# GaN_Fet_ESC_V0_2.net
KiCad netlist of a schematic drawn in EAGLE
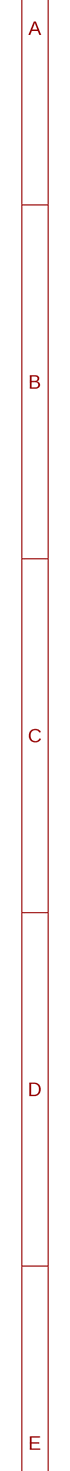
[diagram p0: schematic, sheet 1, part 1 of 2]
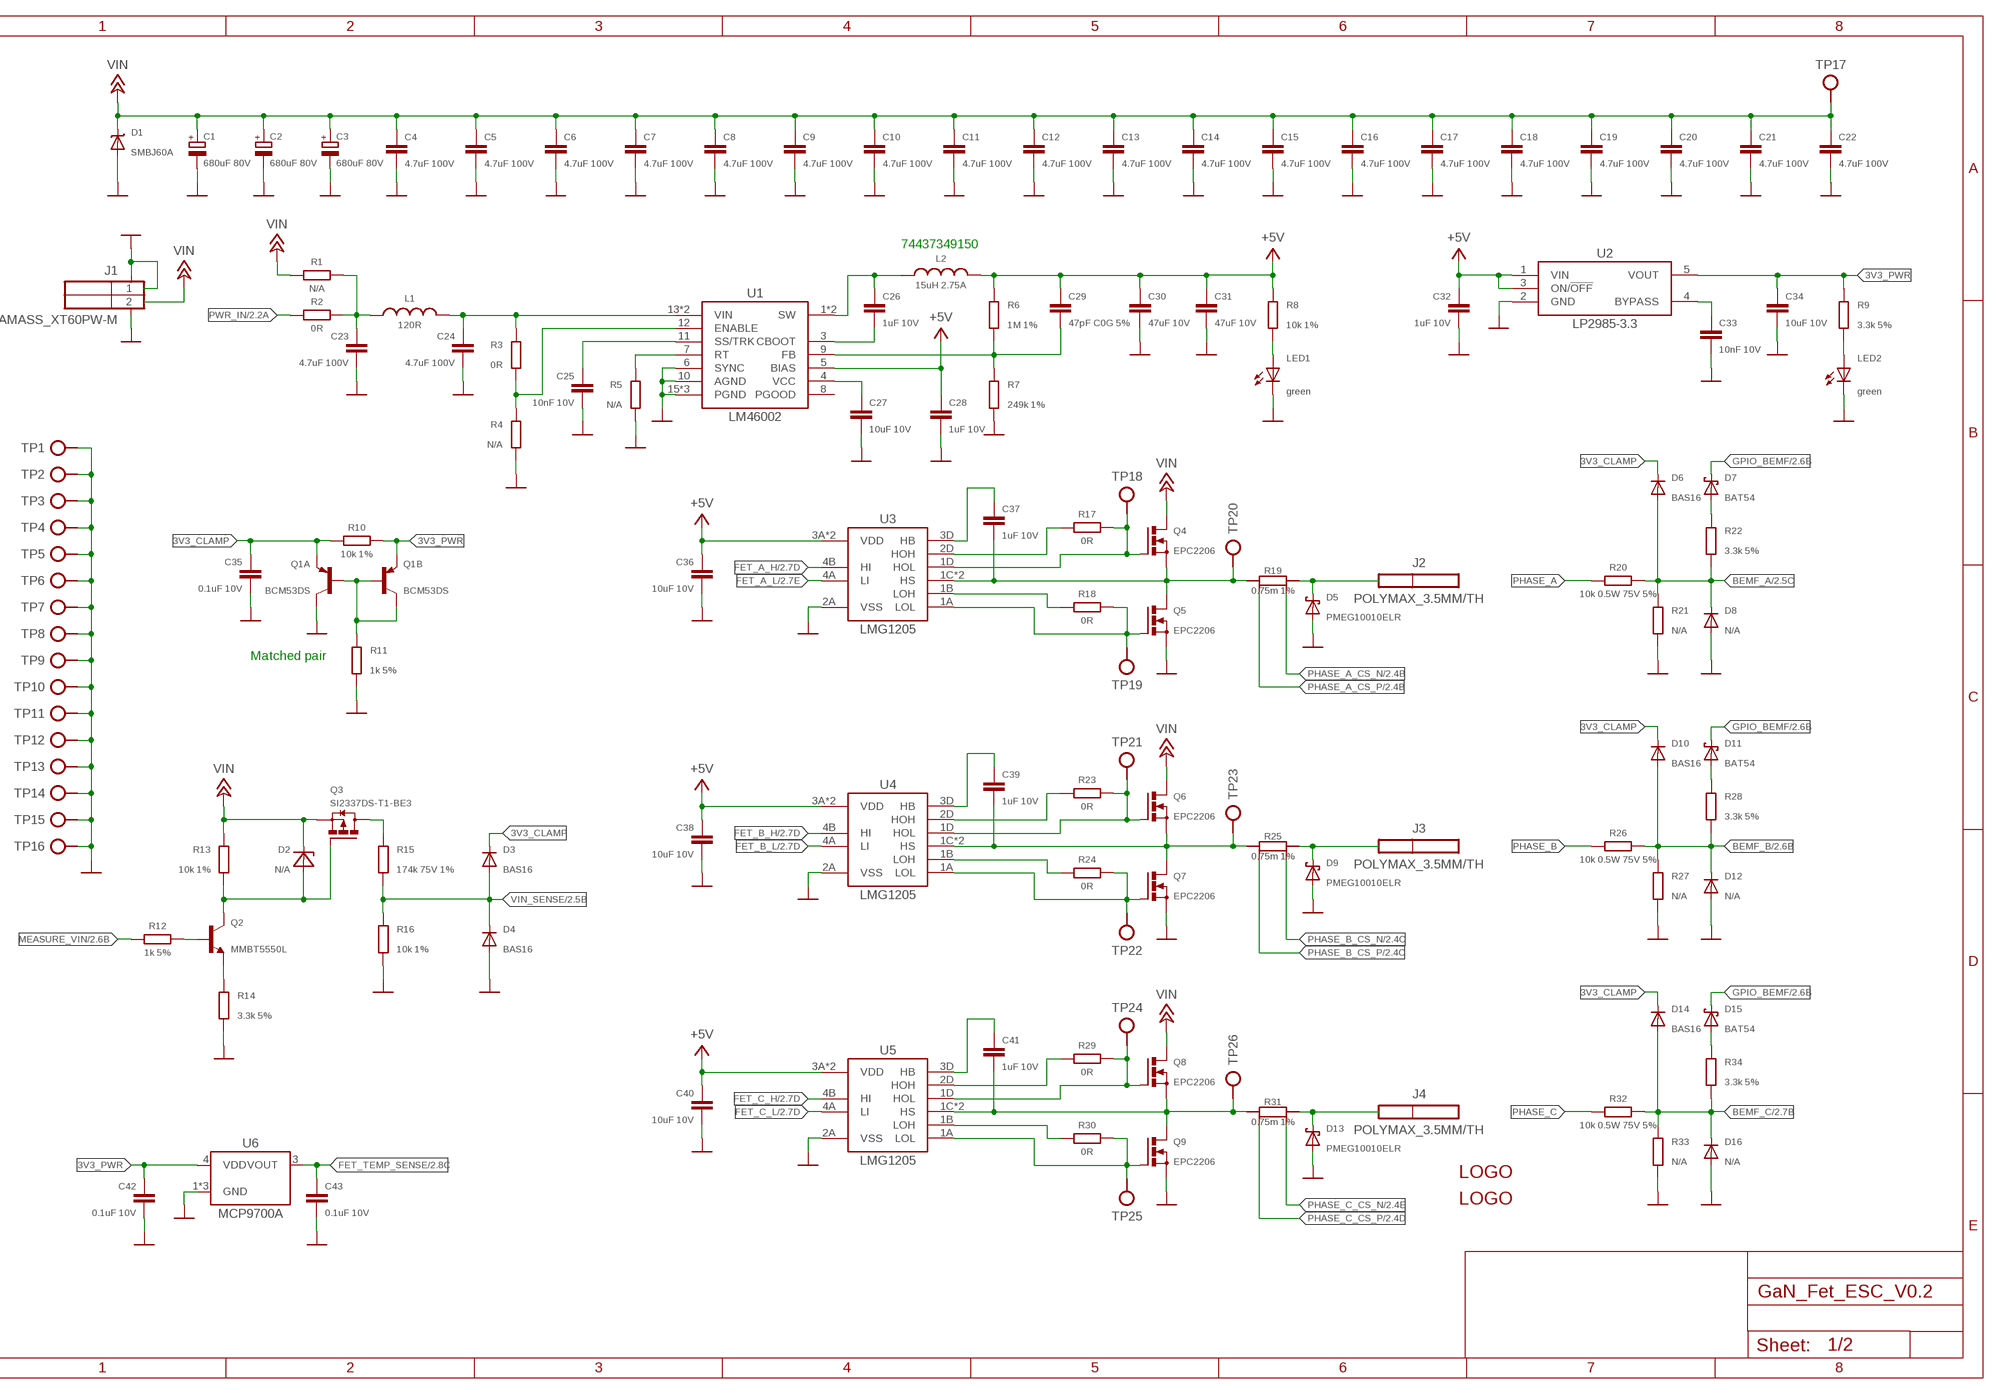
[diagram p1: schematic, sheet 1, part 2 of 2]
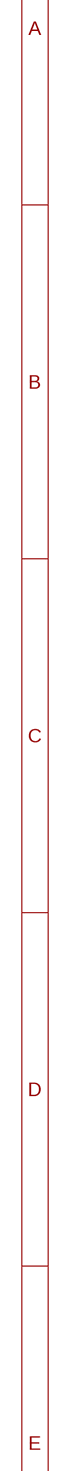
[diagram p2: schematic, sheet 2, part 1 of 2]
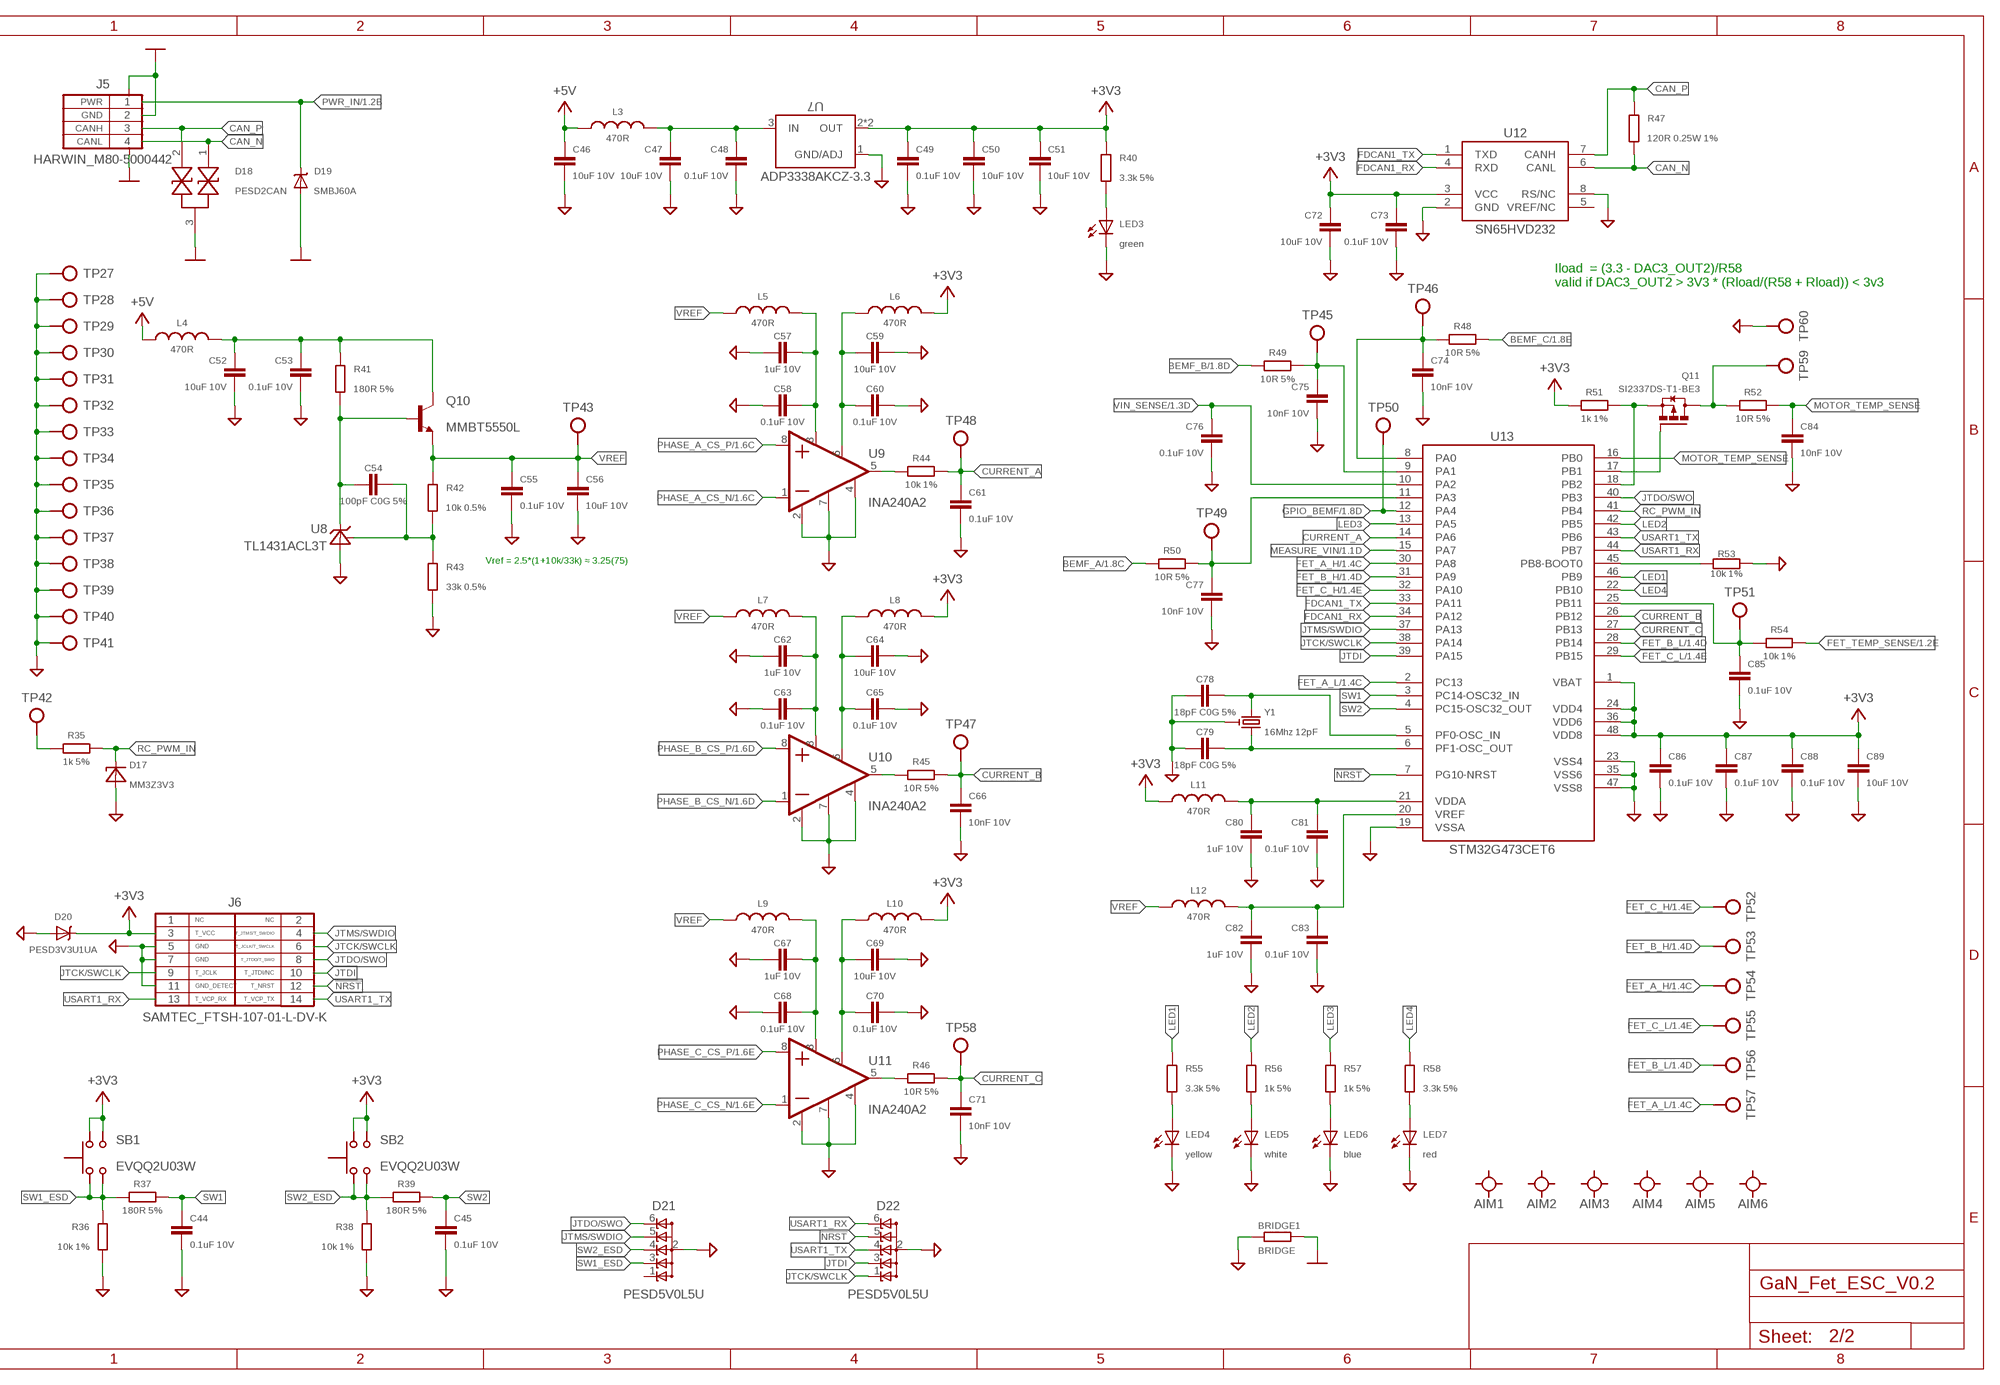
[diagram p3: schematic, sheet 2, part 2 of 2]

(export (version "E")
  (design (tool "Eeschema 10.0.6"))
  (components
    (comp (ref "C1")
      (value "680uF 80V")
      (footprint "eagle-import:C_7.50_16_26.5_4")
      (libsource (lib "eagle-import") (part "CAPACITOR_ELECTROLYTIC4"))
    )
    (comp (ref "C2")
      (value "680uF 80V")
      (footprint "eagle-import:C_7.50_16_26.5_6")
      (libsource (lib "eagle-import") (part "CAPACITOR_ELECTROLYTIC6"))
    )
    (comp (ref "C3")
      (value "680uF 80V")
      (footprint "eagle-import:C_7.50_16_26.5_5")
      (libsource (lib "eagle-import") (part "CAPACITOR_ELECTROLYTIC5"))
    )
    (comp (ref "C4")
      (value "4.7uF 100V")
      (footprint "eagle-import:C1210")
      (libsource (lib "eagle-import") (part "CAPACITOR_CERAMIC/1210"))
    )
    (comp (ref "C5")
      (value "4.7uF 100V")
      (footprint "eagle-import:C1210")
      (libsource (lib "eagle-import") (part "CAPACITOR_CERAMIC/1210"))
    )
    (comp (ref "C6")
      (value "4.7uF 100V")
      (footprint "eagle-import:C1210")
      (libsource (lib "eagle-import") (part "CAPACITOR_CERAMIC/1210"))
    )
    (comp (ref "C7")
      (value "4.7uF 100V")
      (footprint "eagle-import:C1210")
      (libsource (lib "eagle-import") (part "CAPACITOR_CERAMIC/1210"))
    )
    (comp (ref "C8")
      (value "4.7uF 100V")
      (footprint "eagle-import:C1210")
      (libsource (lib "eagle-import") (part "CAPACITOR_CERAMIC/1210"))
    )
    (comp (ref "C9")
      (value "4.7uF 100V")
      (footprint "eagle-import:C1210")
      (libsource (lib "eagle-import") (part "CAPACITOR_CERAMIC/1210"))
    )
    (comp (ref "C10")
      (value "4.7uF 100V")
      (footprint "eagle-import:C1210")
      (libsource (lib "eagle-import") (part "CAPACITOR_CERAMIC/1210"))
    )
    (comp (ref "C11")
      (value "4.7uF 100V")
      (footprint "eagle-import:C1210")
      (libsource (lib "eagle-import") (part "CAPACITOR_CERAMIC/1210"))
    )
    (comp (ref "C12")
      (value "4.7uF 100V")
      (footprint "eagle-import:C1210")
      (libsource (lib "eagle-import") (part "CAPACITOR_CERAMIC/1210"))
    )
    (comp (ref "C13")
      (value "4.7uF 100V")
      (footprint "eagle-import:C1210")
      (libsource (lib "eagle-import") (part "CAPACITOR_CERAMIC/1210"))
    )
    (comp (ref "C14")
      (value "4.7uF 100V")
      (footprint "eagle-import:C1210")
      (libsource (lib "eagle-import") (part "CAPACITOR_CERAMIC/1210"))
    )
    (comp (ref "C15")
      (value "4.7uF 100V")
      (footprint "eagle-import:C1210")
      (libsource (lib "eagle-import") (part "CAPACITOR_CERAMIC/1210"))
    )
    (comp (ref "C16")
      (value "4.7uF 100V")
      (footprint "eagle-import:C1210")
      (libsource (lib "eagle-import") (part "CAPACITOR_CERAMIC/1210"))
    )
    (comp (ref "C17")
      (value "4.7uF 100V")
      (footprint "eagle-import:C1210")
      (libsource (lib "eagle-import") (part "CAPACITOR_CERAMIC/1210"))
    )
    (comp (ref "C18")
      (value "4.7uF 100V")
      (footprint "eagle-import:C1210")
      (libsource (lib "eagle-import") (part "CAPACITOR_CERAMIC/1210"))
    )
    (comp (ref "C19")
      (value "4.7uF 100V")
      (footprint "eagle-import:C1210")
      (libsource (lib "eagle-import") (part "CAPACITOR_CERAMIC/1210"))
    )
    (comp (ref "C20")
      (value "4.7uF 100V")
      (footprint "eagle-import:C1210")
      (libsource (lib "eagle-import") (part "CAPACITOR_CERAMIC/1210"))
    )
    (comp (ref "C21")
      (value "4.7uF 100V")
      (footprint "eagle-import:C1210")
      (libsource (lib "eagle-import") (part "CAPACITOR_CERAMIC/1210"))
    )
    (comp (ref "C22")
      (value "4.7uF 100V")
      (footprint "eagle-import:C1210")
      (libsource (lib "eagle-import") (part "CAPACITOR_CERAMIC/1210"))
    )
    (comp (ref "C23")
      (value "4.7uF 100V")
      (footprint "eagle-import:C1210")
      (libsource (lib "eagle-import") (part "CAPACITOR_CERAMIC/1210"))
    )
    (comp (ref "C24")
      (value "4.7uF 100V")
      (footprint "eagle-import:C1210")
      (libsource (lib "eagle-import") (part "CAPACITOR_CERAMIC/1210"))
    )
    (comp (ref "C25")
      (value "10nF 10V")
      (footprint "eagle-import:C0402")
      (libsource (lib "eagle-import") (part "CAPACITOR_CERAMIC/0402"))
    )
    (comp (ref "C26")
      (value "1uF 10V")
      (footprint "eagle-import:C0402")
      (libsource (lib "eagle-import") (part "CAPACITOR_CERAMIC/0402"))
    )
    (comp (ref "C27")
      (value "10uF 10V")
      (footprint "eagle-import:C0603")
      (libsource (lib "eagle-import") (part "CAPACITOR_CERAMIC/0603"))
    )
    (comp (ref "C28")
      (value "1uF 10V")
      (footprint "eagle-import:C0402")
      (libsource (lib "eagle-import") (part "CAPACITOR_CERAMIC/0402"))
    )
    (comp (ref "C29")
      (value "47pF C0G 5%")
      (footprint "eagle-import:C0402")
      (libsource (lib "eagle-import") (part "CAPACITOR_CERAMIC/0402"))
    )
    (comp (ref "C30")
      (value "47uF 10V")
      (footprint "eagle-import:C1206")
      (libsource (lib "eagle-import") (part "CAPACITOR_CERAMIC/1206"))
    )
    (comp (ref "C31")
      (value "47uF 10V")
      (footprint "eagle-import:C1206")
      (libsource (lib "eagle-import") (part "CAPACITOR_CERAMIC/1206"))
    )
    (comp (ref "C32")
      (value "1uF 10V")
      (footprint "eagle-import:C0402")
      (libsource (lib "eagle-import") (part "CAPACITOR_CERAMIC/0402"))
    )
    (comp (ref "C33")
      (value "10nF 10V")
      (footprint "eagle-import:C0402")
      (libsource (lib "eagle-import") (part "CAPACITOR_CERAMIC/0402"))
    )
    (comp (ref "C34")
      (value "10uF 10V")
      (footprint "eagle-import:C0603")
      (libsource (lib "eagle-import") (part "CAPACITOR_CERAMIC/0603"))
    )
    (comp (ref "C35")
      (value "0.1uF 10V")
      (footprint "eagle-import:C0402")
      (libsource (lib "eagle-import") (part "CAPACITOR_CERAMIC/0402"))
    )
    (comp (ref "C36")
      (value "10uF 10V")
      (footprint "eagle-import:C0603")
      (libsource (lib "eagle-import") (part "CAPACITOR_CERAMIC/0603"))
    )
    (comp (ref "C37")
      (value "1uF 10V")
      (footprint "eagle-import:C0402")
      (libsource (lib "eagle-import") (part "CAPACITOR_CERAMIC/0402"))
    )
    (comp (ref "C38")
      (value "10uF 10V")
      (footprint "eagle-import:C0603")
      (libsource (lib "eagle-import") (part "CAPACITOR_CERAMIC/0603"))
    )
    (comp (ref "C39")
      (value "1uF 10V")
      (footprint "eagle-import:C0402")
      (libsource (lib "eagle-import") (part "CAPACITOR_CERAMIC/0402"))
    )
    (comp (ref "C40")
      (value "10uF 10V")
      (footprint "eagle-import:C0603")
      (libsource (lib "eagle-import") (part "CAPACITOR_CERAMIC/0603"))
    )
    (comp (ref "C41")
      (value "1uF 10V")
      (footprint "eagle-import:C0402")
      (libsource (lib "eagle-import") (part "CAPACITOR_CERAMIC/0402"))
    )
    (comp (ref "C42")
      (value "0.1uF 10V")
      (footprint "eagle-import:C0402")
      (libsource (lib "eagle-import") (part "CAPACITOR_CERAMIC/0402"))
    )
    (comp (ref "C43")
      (value "0.1uF 10V")
      (footprint "eagle-import:C0402")
      (libsource (lib "eagle-import") (part "CAPACITOR_CERAMIC/0402"))
    )
    (comp (ref "D1")
      (value "SMBJ60A")
      (footprint "eagle-import:DO214AA(SMB)")
      (libsource (lib "eagle-import") (part "DIODE_TVS_UNIDIR/SMB"))
    )
    (comp (ref "D2")
      (value "N/A")
      (footprint "eagle-import:SOD323F")
      (libsource (lib "eagle-import") (part "DIODE_ZENER"))
    )
    (comp (ref "D3")
      (value "BAS16")
      (footprint "eagle-import:SOD523")
      (libsource (lib "eagle-import") (part "DIODE/SOD523"))
    )
    (comp (ref "D4")
      (value "BAS16")
      (footprint "eagle-import:SOD523")
      (libsource (lib "eagle-import") (part "DIODE/SOD523"))
    )
    (comp (ref "D5")
      (value "PMEG10010ELR")
      (footprint "eagle-import:SOD123F")
      (libsource (lib "eagle-import") (part "DIODE_SCHOTTKY/SOD123"))
    )
    (comp (ref "D6")
      (value "BAS16")
      (footprint "eagle-import:SOD523")
      (libsource (lib "eagle-import") (part "DIODE/SOD523"))
    )
    (comp (ref "D7")
      (value "BAT54")
      (footprint "eagle-import:SOD523")
      (libsource (lib "eagle-import") (part "DIODE_SCHOTTKY/SOD523"))
    )
    (comp (ref "D8")
      (value "N/A")
      (footprint "eagle-import:SOD523")
      (libsource (lib "eagle-import") (part "DIODE/SOD523"))
    )
    (comp (ref "D9")
      (value "PMEG10010ELR")
      (footprint "eagle-import:SOD123F")
      (libsource (lib "eagle-import") (part "DIODE_SCHOTTKY/SOD123"))
    )
    (comp (ref "D10")
      (value "BAS16")
      (footprint "eagle-import:SOD523")
      (libsource (lib "eagle-import") (part "DIODE/SOD523"))
    )
    (comp (ref "D11")
      (value "BAT54")
      (footprint "eagle-import:SOD523")
      (libsource (lib "eagle-import") (part "DIODE_SCHOTTKY/SOD523"))
    )
    (comp (ref "D12")
      (value "N/A")
      (footprint "eagle-import:SOD523")
      (libsource (lib "eagle-import") (part "DIODE/SOD523"))
    )
    (comp (ref "D13")
      (value "PMEG10010ELR")
      (footprint "eagle-import:SOD123F")
      (libsource (lib "eagle-import") (part "DIODE_SCHOTTKY/SOD123"))
    )
    (comp (ref "D14")
      (value "BAS16")
      (footprint "eagle-import:SOD523")
      (libsource (lib "eagle-import") (part "DIODE/SOD523"))
    )
    (comp (ref "D15")
      (value "BAT54")
      (footprint "eagle-import:SOD523")
      (libsource (lib "eagle-import") (part "DIODE_SCHOTTKY/SOD523"))
    )
    (comp (ref "D16")
      (value "N/A")
      (footprint "eagle-import:SOD523")
      (libsource (lib "eagle-import") (part "DIODE/SOD523"))
    )
    (comp (ref "J1")
      (value "AMASS_XT60PW-M")
      (footprint "eagle-import:AMASS_XT60PW-M")
      (libsource (lib "eagle-import") (part "AMASS_XT60PW-M"))
    )
    (comp (ref "J2")
      (value "POLYMAX_3.5MM/TH")
      (footprint "eagle-import:POLYMAX_3.5MM_TH")
      (libsource (lib "eagle-import") (part "POLYMAX_3.5MM/TH"))
    )
    (comp (ref "J3")
      (value "POLYMAX_3.5MM/TH")
      (footprint "eagle-import:POLYMAX_3.5MM_TH")
      (libsource (lib "eagle-import") (part "POLYMAX_3.5MM/TH"))
    )
    (comp (ref "J4")
      (value "POLYMAX_3.5MM/TH")
      (footprint "eagle-import:POLYMAX_3.5MM_TH")
      (libsource (lib "eagle-import") (part "POLYMAX_3.5MM/TH"))
    )
    (comp (ref "L1")
      (value "120R")
      (footprint "eagle-import:L1206")
      (libsource (lib "eagle-import") (part "INDUCTOR/1206"))
    )
    (comp (ref "L2")
      (value "15uH 2.75A")
      (footprint "eagle-import:WURTH_6.6X6.6")
      (libsource (lib "eagle-import") (part "INDUCTOR/WE-LHMI"))
    )
    (comp (ref "LED1")
      (value "green")
      (footprint "eagle-import:CHIP-LED0603")
      (libsource (lib "eagle-import") (part "LED/0603"))
    )
    (comp (ref "LED2")
      (value "green")
      (footprint "eagle-import:CHIP-LED0603")
      (libsource (lib "eagle-import") (part "LED/0603"))
    )
    (comp (ref "LOGO1")
      (value "LOGO")
      (footprint "eagle-import:LOGO")
      (libsource (lib "eagle-import") (part "LOGO"))
    )
    (comp (ref "LOGO2")
      (value "LOGO")
      (footprint "eagle-import:LOGO")
      (libsource (lib "eagle-import") (part "LOGO"))
    )
    (comp (ref "Q1")
      (value "BCM53DS")
      (footprint "eagle-import:SC-74")
      (libsource (lib "eagle-import") (part "BJT_PNP_DUAL/BCM53DS"))
    )
    (comp (ref "Q2")
      (value "MMBT5550L")
      (footprint "eagle-import:SOT23")
      (libsource (lib "eagle-import") (part "BJT_NPN/SOT23"))
    )
    (comp (ref "Q3")
      (value "SI2337DS-T1-BE3")
      (footprint "eagle-import:SOT23")
      (libsource (lib "eagle-import") (part "P-FET/SOT23"))
    )
    (comp (ref "Q4")
      (value "EPC2206")
      (footprint "eagle-import:EPC2206")
      (libsource (lib "eagle-import") (part "GAN-N-FET"))
    )
    (comp (ref "Q5")
      (value "EPC2206")
      (footprint "eagle-import:EPC2206")
      (libsource (lib "eagle-import") (part "GAN-N-FET"))
    )
    (comp (ref "Q6")
      (value "EPC2206")
      (footprint "eagle-import:EPC2206")
      (libsource (lib "eagle-import") (part "GAN-N-FET"))
    )
    (comp (ref "Q7")
      (value "EPC2206")
      (footprint "eagle-import:EPC2206")
      (libsource (lib "eagle-import") (part "GAN-N-FET"))
    )
    (comp (ref "Q8")
      (value "EPC2206")
      (footprint "eagle-import:EPC2206")
      (libsource (lib "eagle-import") (part "GAN-N-FET"))
    )
    (comp (ref "Q9")
      (value "EPC2206")
      (footprint "eagle-import:EPC2206")
      (libsource (lib "eagle-import") (part "GAN-N-FET"))
    )
    (comp (ref "R1")
      (value "N/A")
      (footprint "eagle-import:R0603")
      (libsource (lib "eagle-import") (part "RESISTOR_SMD/0603"))
    )
    (comp (ref "R2")
      (value "0R")
      (footprint "eagle-import:R0603")
      (libsource (lib "eagle-import") (part "RESISTOR_SMD/0603"))
    )
    (comp (ref "R3")
      (value "0R")
      (footprint "eagle-import:R0603")
      (libsource (lib "eagle-import") (part "RESISTOR_SMD/0603"))
    )
    (comp (ref "R4")
      (value "N/A")
      (footprint "eagle-import:R0402")
      (libsource (lib "eagle-import") (part "RESISTOR_SMD/0402"))
    )
    (comp (ref "R5")
      (value "N/A")
      (footprint "eagle-import:R0402")
      (libsource (lib "eagle-import") (part "RESISTOR_SMD/0402"))
    )
    (comp (ref "R6")
      (value "1M 1%")
      (footprint "eagle-import:R0402")
      (libsource (lib "eagle-import") (part "RESISTOR_SMD/0402"))
    )
    (comp (ref "R7")
      (value "249k 1%")
      (footprint "eagle-import:R0402")
      (libsource (lib "eagle-import") (part "RESISTOR_SMD/0402"))
    )
    (comp (ref "R8")
      (value "10k 1%")
      (footprint "eagle-import:R0402")
      (libsource (lib "eagle-import") (part "RESISTOR_SMD/0402"))
    )
    (comp (ref "R9")
      (value "3.3k 5%")
      (footprint "eagle-import:R0402")
      (libsource (lib "eagle-import") (part "RESISTOR_SMD/0402"))
    )
    (comp (ref "R10")
      (value "10k 1%")
      (footprint "eagle-import:R0402")
      (libsource (lib "eagle-import") (part "RESISTOR_SMD/0402"))
    )
    (comp (ref "R11")
      (value "1k 5%")
      (footprint "eagle-import:R0402")
      (libsource (lib "eagle-import") (part "RESISTOR_SMD/0402"))
    )
    (comp (ref "R12")
      (value "1k 5%")
      (footprint "eagle-import:R0402")
      (libsource (lib "eagle-import") (part "RESISTOR_SMD/0402"))
    )
    (comp (ref "R13")
      (value "10k 1%")
      (footprint "eagle-import:R0402")
      (libsource (lib "eagle-import") (part "RESISTOR_SMD/0402"))
    )
    (comp (ref "R14")
      (value "3.3k 5%")
      (footprint "eagle-import:R0402")
      (libsource (lib "eagle-import") (part "RESISTOR_SMD/0402"))
    )
    (comp (ref "R15")
      (value "174k 75V 1%")
      (footprint "eagle-import:R0603")
      (libsource (lib "eagle-import") (part "RESISTOR_SMD/0603"))
    )
    (comp (ref "R16")
      (value "10k 1%")
      (footprint "eagle-import:R0402")
      (libsource (lib "eagle-import") (part "RESISTOR_SMD/0402"))
    )
    (comp (ref "R17")
      (value "0R")
      (footprint "eagle-import:R0402")
      (libsource (lib "eagle-import") (part "RESISTOR_SMD/0402"))
    )
    (comp (ref "R18")
      (value "0R")
      (footprint "eagle-import:R0402")
      (libsource (lib "eagle-import") (part "RESISTOR_SMD/0402"))
    )
    (comp (ref "R19")
      (value "0.75m 1%")
      (footprint "eagle-import:CSS2H-2512")
      (libsource (lib "eagle-import") (part "RESISTOR_KELVIN/CRF2512"))
    )
    (comp (ref "R20")
      (value "10k 0.5W 75V 5%")
      (footprint "eagle-import:R0805")
      (libsource (lib "eagle-import") (part "RESISTOR_SMD/0805"))
    )
    (comp (ref "R21")
      (value "N/A")
      (footprint "eagle-import:R0402")
      (libsource (lib "eagle-import") (part "RESISTOR_SMD/0402"))
    )
    (comp (ref "R22")
      (value "3.3k 5%")
      (footprint "eagle-import:R0402")
      (libsource (lib "eagle-import") (part "RESISTOR_SMD/0402"))
    )
    (comp (ref "R23")
      (value "0R")
      (footprint "eagle-import:R0402")
      (libsource (lib "eagle-import") (part "RESISTOR_SMD/0402"))
    )
    (comp (ref "R24")
      (value "0R")
      (footprint "eagle-import:R0402")
      (libsource (lib "eagle-import") (part "RESISTOR_SMD/0402"))
    )
    (comp (ref "R25")
      (value "0.75m 1%")
      (footprint "eagle-import:CSS2H-2512")
      (libsource (lib "eagle-import") (part "RESISTOR_KELVIN/CRF2512"))
    )
    (comp (ref "R26")
      (value "10k 0.5W 75V 5%")
      (footprint "eagle-import:R0805")
      (libsource (lib "eagle-import") (part "RESISTOR_SMD/0805"))
    )
    (comp (ref "R27")
      (value "N/A")
      (footprint "eagle-import:R0402")
      (libsource (lib "eagle-import") (part "RESISTOR_SMD/0402"))
    )
    (comp (ref "R28")
      (value "3.3k 5%")
      (footprint "eagle-import:R0402")
      (libsource (lib "eagle-import") (part "RESISTOR_SMD/0402"))
    )
    (comp (ref "R29")
      (value "0R")
      (footprint "eagle-import:R0402")
      (libsource (lib "eagle-import") (part "RESISTOR_SMD/0402"))
    )
    (comp (ref "R30")
      (value "0R")
      (footprint "eagle-import:R0402")
      (libsource (lib "eagle-import") (part "RESISTOR_SMD/0402"))
    )
    (comp (ref "R31")
      (value "0.75m 1%")
      (footprint "eagle-import:CSS2H-2512")
      (libsource (lib "eagle-import") (part "RESISTOR_KELVIN/CRF2512"))
    )
    (comp (ref "R32")
      (value "10k 0.5W 75V 5%")
      (footprint "eagle-import:R0805")
      (libsource (lib "eagle-import") (part "RESISTOR_SMD/0805"))
    )
    (comp (ref "R33")
      (value "N/A")
      (footprint "eagle-import:R0402")
      (libsource (lib "eagle-import") (part "RESISTOR_SMD/0402"))
    )
    (comp (ref "R34")
      (value "3.3k 5%")
      (footprint "eagle-import:R0402")
      (libsource (lib "eagle-import") (part "RESISTOR_SMD/0402"))
    )
    (comp (ref "TP1")
      (value "TESTPOINT0.5MM")
      (footprint "eagle-import:0.5MM")
      (libsource (lib "eagle-import") (part "TESTPOINT0.5MM"))
    )
    (comp (ref "TP2")
      (value "TESTPOINT0.5MM")
      (footprint "eagle-import:0.5MM")
      (libsource (lib "eagle-import") (part "TESTPOINT0.5MM"))
    )
    (comp (ref "TP3")
      (value "TESTPOINT0.5MM")
      (footprint "eagle-import:0.5MM")
      (libsource (lib "eagle-import") (part "TESTPOINT0.5MM"))
    )
    (comp (ref "TP4")
      (value "TESTPOINT0.5MM")
      (footprint "eagle-import:0.5MM")
      (libsource (lib "eagle-import") (part "TESTPOINT0.5MM"))
    )
    (comp (ref "TP5")
      (value "TESTPOINT0.5MM")
      (footprint "eagle-import:0.5MM")
      (libsource (lib "eagle-import") (part "TESTPOINT0.5MM"))
    )
    (comp (ref "TP6")
      (value "TESTPOINT0.5MM")
      (footprint "eagle-import:0.5MM")
      (libsource (lib "eagle-import") (part "TESTPOINT0.5MM"))
    )
    (comp (ref "TP7")
      (value "TESTPOINT0.5MM")
      (footprint "eagle-import:0.5MM")
      (libsource (lib "eagle-import") (part "TESTPOINT0.5MM"))
    )
    (comp (ref "TP8")
      (value "TESTPOINT0.5MM")
      (footprint "eagle-import:0.5MM")
      (libsource (lib "eagle-import") (part "TESTPOINT0.5MM"))
    )
    (comp (ref "TP9")
      (value "TESTPOINT0.5MM")
      (footprint "eagle-import:0.5MM")
      (libsource (lib "eagle-import") (part "TESTPOINT0.5MM"))
    )
    (comp (ref "TP10")
      (value "TESTPOINT0.5MM")
      (footprint "eagle-import:0.5MM")
      (libsource (lib "eagle-import") (part "TESTPOINT0.5MM"))
    )
    (comp (ref "TP11")
      (value "TESTPOINT0.5MM")
      (footprint "eagle-import:0.5MM")
      (libsource (lib "eagle-import") (part "TESTPOINT0.5MM"))
    )
    (comp (ref "TP12")
      (value "TESTPOINT0.5MM")
      (footprint "eagle-import:0.5MM")
      (libsource (lib "eagle-import") (part "TESTPOINT0.5MM"))
    )
    (comp (ref "TP13")
      (value "TESTPOINT0.5MM")
      (footprint "eagle-import:0.5MM")
      (libsource (lib "eagle-import") (part "TESTPOINT0.5MM"))
    )
    (comp (ref "TP14")
      (value "TESTPOINT0.5MM")
      (footprint "eagle-import:0.5MM")
      (libsource (lib "eagle-import") (part "TESTPOINT0.5MM"))
    )
    (comp (ref "TP15")
      (value "TESTPOINT0.5MM")
      (footprint "eagle-import:0.5MM")
      (libsource (lib "eagle-import") (part "TESTPOINT0.5MM"))
    )
    (comp (ref "TP16")
      (value "TESTPOINT0.5MM")
      (footprint "eagle-import:0.5MM")
      (libsource (lib "eagle-import") (part "TESTPOINT0.5MM"))
    )
    (comp (ref "TP17")
      (value "TESTPOINT/0.9MM")
      (footprint "eagle-import:0.9MM")
      (libsource (lib "eagle-import") (part "TESTPOINT/0.9MM"))
    )
    (comp (ref "TP18")
      (value "TESTPOINT/0.9MM")
      (footprint "eagle-import:0.9MM")
      (libsource (lib "eagle-import") (part "TESTPOINT/0.9MM"))
    )
    (comp (ref "TP19")
      (value "TESTPOINT/0.9MM")
      (footprint "eagle-import:0.9MM")
      (libsource (lib "eagle-import") (part "TESTPOINT/0.9MM"))
    )
    (comp (ref "TP20")
      (value "TESTPOINT/0.9MM")
      (footprint "eagle-import:0.9MM")
      (libsource (lib "eagle-import") (part "TESTPOINT/0.9MM"))
    )
    (comp (ref "TP21")
      (value "TESTPOINT/0.9MM")
      (footprint "eagle-import:0.9MM")
      (libsource (lib "eagle-import") (part "TESTPOINT/0.9MM"))
    )
    (comp (ref "TP22")
      (value "TESTPOINT/0.9MM")
      (footprint "eagle-import:0.9MM")
      (libsource (lib "eagle-import") (part "TESTPOINT/0.9MM"))
    )
    (comp (ref "TP23")
      (value "TESTPOINT/0.9MM")
      (footprint "eagle-import:0.9MM")
      (libsource (lib "eagle-import") (part "TESTPOINT/0.9MM"))
    )
    (comp (ref "TP24")
      (value "TESTPOINT/0.9MM")
      (footprint "eagle-import:0.9MM")
      (libsource (lib "eagle-import") (part "TESTPOINT/0.9MM"))
    )
    (comp (ref "TP25")
      (value "TESTPOINT/0.9MM")
      (footprint "eagle-import:0.9MM")
      (libsource (lib "eagle-import") (part "TESTPOINT/0.9MM"))
    )
    (comp (ref "TP26")
      (value "TESTPOINT/0.9MM")
      (footprint "eagle-import:0.9MM")
      (libsource (lib "eagle-import") (part "TESTPOINT/0.9MM"))
    )
    (comp (ref "U1")
      (value "LM46002")
      (footprint "eagle-import:TSS0P16-PAD")
      (libsource (lib "eagle-import") (part "LM46002"))
    )
    (comp (ref "U2")
      (value "LP2985-3.3")
      (footprint "eagle-import:SOT-23-5")
      (libsource (lib "eagle-import") (part "LP2985"))
    )
    (comp (ref "U3")
      (value "LMG1205")
      (footprint "eagle-import:LMG1205")
      (libsource (lib "eagle-import") (part "LMG1205"))
    )
    (comp (ref "U4")
      (value "LMG1205")
      (footprint "eagle-import:LMG1205")
      (libsource (lib "eagle-import") (part "LMG1205"))
    )
    (comp (ref "U5")
      (value "LMG1205")
      (footprint "eagle-import:LMG1205")
      (libsource (lib "eagle-import") (part "LMG1205"))
    )
    (comp (ref "U6")
      (value "MCP9700A")
      (footprint "eagle-import:SC-70-5")
      (libsource (lib "eagle-import") (part "MCP9700/SC-70-5"))
    )
    (comp (ref "AIM1")
      (value "AIM_1_MM")
      (footprint "eagle-import:AIM_1_MM")
      (libsource (lib "eagle-import") (part "AIM_1_MM"))
    )
    (comp (ref "AIM2")
      (value "AIM_1_MM")
      (footprint "eagle-import:AIM_1_MM")
      (libsource (lib "eagle-import") (part "AIM_1_MM"))
    )
    (comp (ref "AIM3")
      (value "AIM_1_MM")
      (footprint "eagle-import:AIM_1_MM")
      (libsource (lib "eagle-import") (part "AIM_1_MM"))
    )
    (comp (ref "AIM4")
      (value "AIM_1_MM")
      (footprint "eagle-import:AIM_1_MM")
      (libsource (lib "eagle-import") (part "AIM_1_MM"))
    )
    (comp (ref "AIM5")
      (value "AIM_1_MM")
      (footprint "eagle-import:AIM_1_MM")
      (libsource (lib "eagle-import") (part "AIM_1_MM"))
    )
    (comp (ref "AIM6")
      (value "AIM_1_MM")
      (footprint "eagle-import:AIM_1_MM")
      (libsource (lib "eagle-import") (part "AIM_1_MM"))
    )
    (comp (ref "BRIDGE1")
      (value "BRIDGE")
      (footprint "eagle-import:BRIDGE")
      (libsource (lib "eagle-import") (part "BRIDGE"))
    )
    (comp (ref "C44")
      (value "0.1uF 10V")
      (footprint "eagle-import:C0402")
      (libsource (lib "eagle-import") (part "CAPACITOR_CERAMIC/0402"))
    )
    (comp (ref "C45")
      (value "0.1uF 10V")
      (footprint "eagle-import:C0402")
      (libsource (lib "eagle-import") (part "CAPACITOR_CERAMIC/0402"))
    )
    (comp (ref "C46")
      (value "10uF 10V")
      (footprint "eagle-import:C0603")
      (libsource (lib "eagle-import") (part "CAPACITOR_CERAMIC/0603"))
    )
    (comp (ref "C47")
      (value "10uF 10V")
      (footprint "eagle-import:C0603")
      (libsource (lib "eagle-import") (part "CAPACITOR_CERAMIC/0603"))
    )
    (comp (ref "C48")
      (value "0.1uF 10V")
      (footprint "eagle-import:C0402")
      (libsource (lib "eagle-import") (part "CAPACITOR_CERAMIC/0402"))
    )
    (comp (ref "C49")
      (value "0.1uF 10V")
      (footprint "eagle-import:C0402")
      (libsource (lib "eagle-import") (part "CAPACITOR_CERAMIC/0402"))
    )
    (comp (ref "C50")
      (value "10uF 10V")
      (footprint "eagle-import:C0603")
      (libsource (lib "eagle-import") (part "CAPACITOR_CERAMIC/0603"))
    )
    (comp (ref "C51")
      (value "10uF 10V")
      (footprint "eagle-import:C0603")
      (libsource (lib "eagle-import") (part "CAPACITOR_CERAMIC/0603"))
    )
    (comp (ref "C52")
      (value "10uF 10V")
      (footprint "eagle-import:C0603")
      (libsource (lib "eagle-import") (part "CAPACITOR_CERAMIC/0603"))
    )
    (comp (ref "C53")
      (value "0.1uF 10V")
      (footprint "eagle-import:C0402")
      (libsource (lib "eagle-import") (part "CAPACITOR_CERAMIC/0402"))
    )
    (comp (ref "C54")
      (value "100pF C0G 5%")
      (footprint "eagle-import:C0402")
      (libsource (lib "eagle-import") (part "CAPACITOR_CERAMIC/0402"))
    )
    (comp (ref "C55")
      (value "0.1uF 10V")
      (footprint "eagle-import:C0402")
      (libsource (lib "eagle-import") (part "CAPACITOR_CERAMIC/0402"))
    )
    (comp (ref "C56")
      (value "10uF 10V")
      (footprint "eagle-import:C0603")
      (libsource (lib "eagle-import") (part "CAPACITOR_CERAMIC/0603"))
    )
    (comp (ref "C57")
      (value "1uF 10V")
      (footprint "eagle-import:C0402")
      (libsource (lib "eagle-import") (part "CAPACITOR_CERAMIC/0402"))
    )
    (comp (ref "C58")
      (value "0.1uF 10V")
      (footprint "eagle-import:C0402")
      (libsource (lib "eagle-import") (part "CAPACITOR_CERAMIC/0402"))
    )
    (comp (ref "C59")
      (value "10uF 10V")
      (footprint "eagle-import:C0603")
      (libsource (lib "eagle-import") (part "CAPACITOR_CERAMIC/0603"))
    )
    (comp (ref "C60")
      (value "0.1uF 10V")
      (footprint "eagle-import:C0402")
      (libsource (lib "eagle-import") (part "CAPACITOR_CERAMIC/0402"))
    )
    (comp (ref "C61")
      (value "0.1uF 10V")
      (footprint "eagle-import:C0402")
      (libsource (lib "eagle-import") (part "CAPACITOR_CERAMIC/0402"))
    )
    (comp (ref "C62")
      (value "1uF 10V")
      (footprint "eagle-import:C0402")
      (libsource (lib "eagle-import") (part "CAPACITOR_CERAMIC/0402"))
    )
    (comp (ref "C63")
      (value "0.1uF 10V")
      (footprint "eagle-import:C0402")
      (libsource (lib "eagle-import") (part "CAPACITOR_CERAMIC/0402"))
    )
    (comp (ref "C64")
      (value "10uF 10V")
      (footprint "eagle-import:C0603")
      (libsource (lib "eagle-import") (part "CAPACITOR_CERAMIC/0603"))
    )
    (comp (ref "C65")
      (value "0.1uF 10V")
      (footprint "eagle-import:C0402")
      (libsource (lib "eagle-import") (part "CAPACITOR_CERAMIC/0402"))
    )
    (comp (ref "C66")
      (value "10nF 10V")
      (footprint "eagle-import:C0402")
      (libsource (lib "eagle-import") (part "CAPACITOR_CERAMIC/0402"))
    )
    (comp (ref "C67")
      (value "1uF 10V")
      (footprint "eagle-import:C0402")
      (libsource (lib "eagle-import") (part "CAPACITOR_CERAMIC/0402"))
    )
    (comp (ref "C68")
      (value "0.1uF 10V")
      (footprint "eagle-import:C0402")
      (libsource (lib "eagle-import") (part "CAPACITOR_CERAMIC/0402"))
    )
    (comp (ref "C69")
      (value "10uF 10V")
      (footprint "eagle-import:C0603")
      (libsource (lib "eagle-import") (part "CAPACITOR_CERAMIC/0603"))
    )
    (comp (ref "C70")
      (value "0.1uF 10V")
      (footprint "eagle-import:C0402")
      (libsource (lib "eagle-import") (part "CAPACITOR_CERAMIC/0402"))
    )
    (comp (ref "C71")
      (value "10nF 10V")
      (footprint "eagle-import:C0402")
      (libsource (lib "eagle-import") (part "CAPACITOR_CERAMIC/0402"))
    )
    (comp (ref "C72")
      (value "10uF 10V")
      (footprint "eagle-import:C0603")
      (libsource (lib "eagle-import") (part "CAPACITOR_CERAMIC/0603"))
    )
    (comp (ref "C73")
      (value "0.1uF 10V")
      (footprint "eagle-import:C0402")
      (libsource (lib "eagle-import") (part "CAPACITOR_CERAMIC/0402"))
    )
    (comp (ref "C74")
      (value "10nF 10V")
      (footprint "eagle-import:C0402")
      (libsource (lib "eagle-import") (part "CAPACITOR_CERAMIC/0402"))
    )
    (comp (ref "C75")
      (value "10nF 10V")
      (footprint "eagle-import:C0402")
      (libsource (lib "eagle-import") (part "CAPACITOR_CERAMIC/0402"))
    )
    (comp (ref "C76")
      (value "0.1uF 10V")
      (footprint "eagle-import:C0402")
      (libsource (lib "eagle-import") (part "CAPACITOR_CERAMIC/0402"))
    )
    (comp (ref "C77")
      (value "10nF 10V")
      (footprint "eagle-import:C0402")
      (libsource (lib "eagle-import") (part "CAPACITOR_CERAMIC/0402"))
    )
    (comp (ref "C78")
      (value "18pF C0G 5%")
      (footprint "eagle-import:C0402")
      (libsource (lib "eagle-import") (part "CAPACITOR_CERAMIC/0402"))
    )
    (comp (ref "C79")
      (value "18pF C0G 5%")
      (footprint "eagle-import:C0402")
      (libsource (lib "eagle-import") (part "CAPACITOR_CERAMIC/0402"))
    )
    (comp (ref "C80")
      (value "1uF 10V")
      (footprint "eagle-import:C0402")
      (libsource (lib "eagle-import") (part "CAPACITOR_CERAMIC/0402"))
    )
    (comp (ref "C81")
      (value "0.1uF 10V")
      (footprint "eagle-import:C0402")
      (libsource (lib "eagle-import") (part "CAPACITOR_CERAMIC/0402"))
    )
    (comp (ref "C82")
      (value "1uF 10V")
      (footprint "eagle-import:C0402")
      (libsource (lib "eagle-import") (part "CAPACITOR_CERAMIC/0402"))
    )
    (comp (ref "C83")
      (value "0.1uF 10V")
      (footprint "eagle-import:C0402")
      (libsource (lib "eagle-import") (part "CAPACITOR_CERAMIC/0402"))
    )
    (comp (ref "C84")
      (value "10nF 10V")
      (footprint "eagle-import:C0402")
      (libsource (lib "eagle-import") (part "CAPACITOR_CERAMIC/0402"))
    )
    (comp (ref "C85")
      (value "0.1uF 10V")
      (footprint "eagle-import:C0402")
      (libsource (lib "eagle-import") (part "CAPACITOR_CERAMIC/0402"))
    )
    (comp (ref "C86")
      (value "0.1uF 10V")
      (footprint "eagle-import:C0402")
      (libsource (lib "eagle-import") (part "CAPACITOR_CERAMIC/0402"))
    )
    (comp (ref "C87")
      (value "0.1uF 10V")
      (footprint "eagle-import:C0402")
      (libsource (lib "eagle-import") (part "CAPACITOR_CERAMIC/0402"))
    )
    (comp (ref "C88")
      (value "0.1uF 10V")
      (footprint "eagle-import:C0402")
      (libsource (lib "eagle-import") (part "CAPACITOR_CERAMIC/0402"))
    )
    (comp (ref "C89")
      (value "10uF 10V")
      (footprint "eagle-import:C0603")
      (libsource (lib "eagle-import") (part "CAPACITOR_CERAMIC/0603"))
    )
    (comp (ref "D17")
      (value "MM3Z3V3")
      (footprint "eagle-import:SOD323F")
      (libsource (lib "eagle-import") (part "DIODE_ZENER"))
    )
    (comp (ref "D18")
      (value "PESD2CAN")
      (footprint "eagle-import:SOT23")
      (libsource (lib "eagle-import") (part "DIODE_TVS_DUAL"))
    )
    (comp (ref "D19")
      (value "SMBJ60A")
      (footprint "eagle-import:DO214AA(SMB)")
      (libsource (lib "eagle-import") (part "DIODE_TVS_UNIDIR/SMB"))
    )
    (comp (ref "D20")
      (value "PESD3V3U1UA")
      (footprint "eagle-import:SOD323F")
      (libsource (lib "eagle-import") (part "DIODE_TVS_UNIDIR/SOD323"))
    )
    (comp (ref "D21")
      (value "PESD5V0L5U")
      (footprint "eagle-import:SC-70-6")
      (libsource (lib "eagle-import") (part "ESD_5"))
    )
    (comp (ref "D22")
      (value "PESD5V0L5U")
      (footprint "eagle-import:SC-70-6")
      (libsource (lib "eagle-import") (part "ESD_5"))
    )
    (comp (ref "J5")
      (value "HARWIN_M80-5000442")
      (footprint "eagle-import:HARWIN_M80-5000442")
      (libsource (lib "eagle-import") (part "HARWIN_M80-5000442"))
    )
    (comp (ref "J6")
      (value "SAMTEC_FTSH-107-01-L-DV-K")
      (footprint "eagle-import:SAMTEC_FTSH-107-01-L-DV-K")
      (libsource (lib "eagle-import") (part "SAMTEC_FTSH-107-01-L-DV-K"))
    )
    (comp (ref "L3")
      (value "470R")
      (footprint "eagle-import:L0603")
      (libsource (lib "eagle-import") (part "INDUCTOR/0603"))
    )
    (comp (ref "L4")
      (value "470R")
      (footprint "eagle-import:L0603")
      (libsource (lib "eagle-import") (part "INDUCTOR/0603"))
    )
    (comp (ref "L5")
      (value "470R")
      (footprint "eagle-import:L0603")
      (libsource (lib "eagle-import") (part "INDUCTOR/0603"))
    )
    (comp (ref "L6")
      (value "470R")
      (footprint "eagle-import:L0603")
      (libsource (lib "eagle-import") (part "INDUCTOR/0603"))
    )
    (comp (ref "L7")
      (value "470R")
      (footprint "eagle-import:L0603")
      (libsource (lib "eagle-import") (part "INDUCTOR/0603"))
    )
    (comp (ref "L8")
      (value "470R")
      (footprint "eagle-import:L0603")
      (libsource (lib "eagle-import") (part "INDUCTOR/0603"))
    )
    (comp (ref "L9")
      (value "470R")
      (footprint "eagle-import:L0603")
      (libsource (lib "eagle-import") (part "INDUCTOR/0603"))
    )
    (comp (ref "L10")
      (value "470R")
      (footprint "eagle-import:L0603")
      (libsource (lib "eagle-import") (part "INDUCTOR/0603"))
    )
    (comp (ref "L11")
      (value "470R")
      (footprint "eagle-import:L0603")
      (libsource (lib "eagle-import") (part "INDUCTOR/0603"))
    )
    (comp (ref "L12")
      (value "470R")
      (footprint "eagle-import:L0603")
      (libsource (lib "eagle-import") (part "INDUCTOR/0603"))
    )
    (comp (ref "LED3")
      (value "green")
      (footprint "eagle-import:CHIP-LED0603")
      (libsource (lib "eagle-import") (part "LED/0603"))
    )
    (comp (ref "LED4")
      (value "yellow")
      (footprint "eagle-import:CHIP-LED0603")
      (libsource (lib "eagle-import") (part "LED/0603"))
    )
    (comp (ref "LED5")
      (value "white")
      (footprint "eagle-import:CHIP-LED0603")
      (libsource (lib "eagle-import") (part "LED/0603"))
    )
    (comp (ref "LED6")
      (value "blue")
      (footprint "eagle-import:CHIP-LED0603")
      (libsource (lib "eagle-import") (part "LED/0603"))
    )
    (comp (ref "LED7")
      (value "red")
      (footprint "eagle-import:CHIP-LED0603")
      (libsource (lib "eagle-import") (part "LED/0603"))
    )
    (comp (ref "Q10")
      (value "MMBT5550L")
      (footprint "eagle-import:SOT23")
      (libsource (lib "eagle-import") (part "BJT_NPN/SOT23"))
    )
    (comp (ref "Q11")
      (value "SI2337DS-T1-BE3")
      (footprint "eagle-import:SOT23")
      (libsource (lib "eagle-import") (part "P-FET/SOT23"))
    )
    (comp (ref "R35")
      (value "1k 5%")
      (footprint "eagle-import:R0402")
      (libsource (lib "eagle-import") (part "RESISTOR_SMD/0402"))
    )
    (comp (ref "R36")
      (value "10k 1%")
      (footprint "eagle-import:R0402")
      (libsource (lib "eagle-import") (part "RESISTOR_SMD/0402"))
    )
    (comp (ref "R37")
      (value "180R 5%")
      (footprint "eagle-import:R0402")
      (libsource (lib "eagle-import") (part "RESISTOR_SMD/0402"))
    )
    (comp (ref "R38")
      (value "10k 1%")
      (footprint "eagle-import:R0402")
      (libsource (lib "eagle-import") (part "RESISTOR_SMD/0402"))
    )
    (comp (ref "R39")
      (value "180R 5%")
      (footprint "eagle-import:R0402")
      (libsource (lib "eagle-import") (part "RESISTOR_SMD/0402"))
    )
    (comp (ref "R40")
      (value "3.3k 5%")
      (footprint "eagle-import:R0402")
      (libsource (lib "eagle-import") (part "RESISTOR_SMD/0402"))
    )
    (comp (ref "R41")
      (value "180R 5%")
      (footprint "eagle-import:R0402")
      (libsource (lib "eagle-import") (part "RESISTOR_SMD/0402"))
    )
    (comp (ref "R42")
      (value "10k 0.5%")
      (footprint "eagle-import:R0603")
      (libsource (lib "eagle-import") (part "RESISTOR_SMD/0603"))
    )
    (comp (ref "R43")
      (value "33k 0.5%")
      (footprint "eagle-import:R0603")
      (libsource (lib "eagle-import") (part "RESISTOR_SMD/0603"))
    )
    (comp (ref "R44")
      (value "10k 1%")
      (footprint "eagle-import:R0402")
      (libsource (lib "eagle-import") (part "RESISTOR_SMD/0402"))
    )
    (comp (ref "R45")
      (value "10R 5%")
      (footprint "eagle-import:R0402")
      (libsource (lib "eagle-import") (part "RESISTOR_SMD/0402"))
    )
    (comp (ref "R46")
      (value "10R 5%")
      (footprint "eagle-import:R0402")
      (libsource (lib "eagle-import") (part "RESISTOR_SMD/0402"))
    )
    (comp (ref "R47")
      (value "120R 0.25W 1%")
      (footprint "eagle-import:R0805")
      (libsource (lib "eagle-import") (part "RESISTOR_SMD/0805"))
    )
    (comp (ref "R48")
      (value "10R 5%")
      (footprint "eagle-import:R0402")
      (libsource (lib "eagle-import") (part "RESISTOR_SMD/0402"))
    )
    (comp (ref "R49")
      (value "10R 5%")
      (footprint "eagle-import:R0402")
      (libsource (lib "eagle-import") (part "RESISTOR_SMD/0402"))
    )
    (comp (ref "R50")
      (value "10R 5%")
      (footprint "eagle-import:R0402")
      (libsource (lib "eagle-import") (part "RESISTOR_SMD/0402"))
    )
    (comp (ref "R51")
      (value "1k 1%")
      (footprint "eagle-import:R0402")
      (libsource (lib "eagle-import") (part "RESISTOR_SMD/0402"))
    )
    (comp (ref "R52")
      (value "10R 5%")
      (footprint "eagle-import:R0402")
      (libsource (lib "eagle-import") (part "RESISTOR_SMD/0402"))
    )
    (comp (ref "R53")
      (value "10k 1%")
      (footprint "eagle-import:R0402")
      (libsource (lib "eagle-import") (part "RESISTOR_SMD/0402"))
    )
    (comp (ref "R54")
      (value "10k 1%")
      (footprint "eagle-import:R0402")
      (libsource (lib "eagle-import") (part "RESISTOR_SMD/0402"))
    )
    (comp (ref "R55")
      (value "3.3k 5%")
      (footprint "eagle-import:R0402")
      (libsource (lib "eagle-import") (part "RESISTOR_SMD/0402"))
    )
    (comp (ref "R56")
      (value "1k 5%")
      (footprint "eagle-import:R0402")
      (libsource (lib "eagle-import") (part "RESISTOR_SMD/0402"))
    )
    (comp (ref "R57")
      (value "1k 5%")
      (footprint "eagle-import:R0402")
      (libsource (lib "eagle-import") (part "RESISTOR_SMD/0402"))
    )
    (comp (ref "R58")
      (value "3.3k 5%")
      (footprint "eagle-import:R0402")
      (libsource (lib "eagle-import") (part "RESISTOR_SMD/0402"))
    )
    (comp (ref "SB1")
      (value "EVQQ2U03W")
      (footprint "eagle-import:EVQQ2U03W")
      (libsource (lib "eagle-import") (part "PUSH_BUTTONSMD5.2X5.2"))
    )
    (comp (ref "SB2")
      (value "EVQQ2U03W")
      (footprint "eagle-import:EVQQ2U03W")
      (libsource (lib "eagle-import") (part "PUSH_BUTTONSMD5.2X5.2"))
    )
    (comp (ref "TP27")
      (value "TESTPOINT0.5MM")
      (footprint "eagle-import:0.5MM")
      (libsource (lib "eagle-import") (part "TESTPOINT0.5MM"))
    )
    (comp (ref "TP28")
      (value "TESTPOINT0.5MM")
      (footprint "eagle-import:0.5MM")
      (libsource (lib "eagle-import") (part "TESTPOINT0.5MM"))
    )
    (comp (ref "TP29")
      (value "TESTPOINT0.5MM")
      (footprint "eagle-import:0.5MM")
      (libsource (lib "eagle-import") (part "TESTPOINT0.5MM"))
    )
    (comp (ref "TP30")
      (value "TESTPOINT0.5MM")
      (footprint "eagle-import:0.5MM")
      (libsource (lib "eagle-import") (part "TESTPOINT0.5MM"))
    )
    (comp (ref "TP31")
      (value "TESTPOINT0.5MM")
      (footprint "eagle-import:0.5MM")
      (libsource (lib "eagle-import") (part "TESTPOINT0.5MM"))
    )
    (comp (ref "TP32")
      (value "TESTPOINT0.5MM")
      (footprint "eagle-import:0.5MM")
      (libsource (lib "eagle-import") (part "TESTPOINT0.5MM"))
    )
    (comp (ref "TP33")
      (value "TESTPOINT0.5MM")
      (footprint "eagle-import:0.5MM")
      (libsource (lib "eagle-import") (part "TESTPOINT0.5MM"))
    )
    (comp (ref "TP34")
      (value "TESTPOINT0.5MM")
      (footprint "eagle-import:0.5MM")
      (libsource (lib "eagle-import") (part "TESTPOINT0.5MM"))
    )
    (comp (ref "TP35")
      (value "TESTPOINT0.5MM")
      (footprint "eagle-import:0.5MM")
      (libsource (lib "eagle-import") (part "TESTPOINT0.5MM"))
    )
    (comp (ref "TP36")
      (value "TESTPOINT0.5MM")
      (footprint "eagle-import:0.5MM")
      (libsource (lib "eagle-import") (part "TESTPOINT0.5MM"))
    )
    (comp (ref "TP37")
      (value "TESTPOINT0.5MM")
      (footprint "eagle-import:0.5MM")
      (libsource (lib "eagle-import") (part "TESTPOINT0.5MM"))
    )
    (comp (ref "TP38")
      (value "TESTPOINT0.5MM")
      (footprint "eagle-import:0.5MM")
      (libsource (lib "eagle-import") (part "TESTPOINT0.5MM"))
    )
    (comp (ref "TP39")
      (value "TESTPOINT0.5MM")
      (footprint "eagle-import:0.5MM")
      (libsource (lib "eagle-import") (part "TESTPOINT0.5MM"))
    )
    (comp (ref "TP40")
      (value "TESTPOINT0.5MM")
      (footprint "eagle-import:0.5MM")
      (libsource (lib "eagle-import") (part "TESTPOINT0.5MM"))
    )
    (comp (ref "TP41")
      (value "TESTPOINT/0.9MM")
      (footprint "eagle-import:0.9MM")
      (libsource (lib "eagle-import") (part "TESTPOINT/0.9MM"))
    )
    (comp (ref "TP42")
      (value "TESTPOINT/0.9MM")
      (footprint "eagle-import:0.9MM")
      (libsource (lib "eagle-import") (part "TESTPOINT/0.9MM"))
    )
    (comp (ref "TP43")
      (value "TESTPOINT/0.9MM")
      (footprint "eagle-import:0.9MM")
      (libsource (lib "eagle-import") (part "TESTPOINT/0.9MM"))
    )
    (comp (ref "TP45")
      (value "TESTPOINT/0.9MM")
      (footprint "eagle-import:0.9MM")
      (libsource (lib "eagle-import") (part "TESTPOINT/0.9MM"))
    )
    (comp (ref "TP46")
      (value "TESTPOINT/0.9MM")
      (footprint "eagle-import:0.9MM")
      (libsource (lib "eagle-import") (part "TESTPOINT/0.9MM"))
    )
    (comp (ref "TP47")
      (value "TESTPOINT/0.9MM")
      (footprint "eagle-import:0.9MM")
      (libsource (lib "eagle-import") (part "TESTPOINT/0.9MM"))
    )
    (comp (ref "TP48")
      (value "TESTPOINT/0.9MM")
      (footprint "eagle-import:0.9MM")
      (libsource (lib "eagle-import") (part "TESTPOINT/0.9MM"))
    )
    (comp (ref "TP49")
      (value "TESTPOINT/0.9MM")
      (footprint "eagle-import:0.9MM")
      (libsource (lib "eagle-import") (part "TESTPOINT/0.9MM"))
    )
    (comp (ref "TP50")
      (value "TESTPOINT/0.9MM")
      (footprint "eagle-import:0.9MM")
      (libsource (lib "eagle-import") (part "TESTPOINT/0.9MM"))
    )
    (comp (ref "TP51")
      (value "TESTPOINT/0.9MM")
      (footprint "eagle-import:0.9MM")
      (libsource (lib "eagle-import") (part "TESTPOINT/0.9MM"))
    )
    (comp (ref "TP52")
      (value "TESTPOINT/0.9MM")
      (footprint "eagle-import:0.9MM")
      (libsource (lib "eagle-import") (part "TESTPOINT/0.9MM"))
    )
    (comp (ref "TP53")
      (value "TESTPOINT/0.9MM")
      (footprint "eagle-import:0.9MM")
      (libsource (lib "eagle-import") (part "TESTPOINT/0.9MM"))
    )
    (comp (ref "TP54")
      (value "TESTPOINT/0.9MM")
      (footprint "eagle-import:0.9MM")
      (libsource (lib "eagle-import") (part "TESTPOINT/0.9MM"))
    )
    (comp (ref "TP55")
      (value "TESTPOINT/0.9MM")
      (footprint "eagle-import:0.9MM")
      (libsource (lib "eagle-import") (part "TESTPOINT/0.9MM"))
    )
    (comp (ref "TP56")
      (value "TESTPOINT/0.9MM")
      (footprint "eagle-import:0.9MM")
      (libsource (lib "eagle-import") (part "TESTPOINT/0.9MM"))
    )
    (comp (ref "TP57")
      (value "TESTPOINT/0.9MM")
      (footprint "eagle-import:0.9MM")
      (libsource (lib "eagle-import") (part "TESTPOINT/0.9MM"))
    )
    (comp (ref "TP58")
      (value "TESTPOINT/0.9MM")
      (footprint "eagle-import:0.9MM")
      (libsource (lib "eagle-import") (part "TESTPOINT/0.9MM"))
    )
    (comp (ref "TP59")
      (value "TESTPOINT/0.9MM")
      (footprint "eagle-import:0.9MM")
      (libsource (lib "eagle-import") (part "TESTPOINT/0.9MM"))
    )
    (comp (ref "TP60")
      (value "TESTPOINT/0.9MM")
      (footprint "eagle-import:0.9MM")
      (libsource (lib "eagle-import") (part "TESTPOINT/0.9MM"))
    )
    (comp (ref "U7")
      (value "ADP3338AKCZ-3.3")
      (footprint "eagle-import:SOT223")
      (libsource (lib "eagle-import") (part "LM317"))
    )
    (comp (ref "U8")
      (value "TL1431ACL3T")
      (footprint "eagle-import:SOT23")
      (libsource (lib "eagle-import") (part "TL431"))
    )
    (comp (ref "U9")
      (value "INA240A2")
      (footprint "eagle-import:SOIC-8")
      (libsource (lib "eagle-import") (part "INA240/SOIC-8"))
    )
    (comp (ref "U10")
      (value "INA240A2")
      (footprint "eagle-import:SOIC-8")
      (libsource (lib "eagle-import") (part "INA240/SOIC-8"))
    )
    (comp (ref "U11")
      (value "INA240A2")
      (footprint "eagle-import:SOIC-8")
      (libsource (lib "eagle-import") (part "INA240/SOIC-8"))
    )
    (comp (ref "U12")
      (value "SN65HVD232")
      (footprint "eagle-import:SOIC-8")
      (libsource (lib "eagle-import") (part "SN65HVD23X"))
    )
    (comp (ref "U13")
      (value "STM32G473CET6")
      (footprint "eagle-import:LQFP-48")
      (libsource (lib "eagle-import") (part "STM32G4_48"))
    )
    (comp (ref "Y1")
      (value "16Mhz 12pF")
      (footprint "eagle-import:CRYSTAL_SMD_3.2X2.5MM")
      (libsource (lib "eagle-import") (part "CRYSTAL_GROUNDED/SMD_3.2X2.5MM"))
    )
  )
  (nets
    (net (code "1") (name "+3V3") (class "Default")
      (node (ref "C49") (pin "1") (pinfunction "1_1") (pintype "passive"))
      (node (ref "C50") (pin "1") (pinfunction "1_1") (pintype "passive"))
      (node (ref "C51") (pin "1") (pinfunction "1_1") (pintype "passive"))
      (node (ref "C72") (pin "1") (pinfunction "1_1") (pintype "passive"))
      (node (ref "C73") (pin "1") (pinfunction "1_1") (pintype "passive"))
      (node (ref "C86") (pin "1") (pinfunction "1_1") (pintype "passive"))
      (node (ref "C87") (pin "1") (pinfunction "1_1") (pintype "passive"))
      (node (ref "C88") (pin "1") (pinfunction "1_1") (pintype "passive"))
      (node (ref "C89") (pin "1") (pinfunction "1_1") (pintype "passive"))
      (node (ref "D20") (pin "C") (pinfunction "C_C") (pintype "passive"))
      (node (ref "J6") (pin "3") (pinfunction "3_3") (pintype "bidirectional"))
      (node (ref "L10") (pin "1") (pinfunction "1_1") (pintype "passive"))
      (node (ref "L11") (pin "1") (pinfunction "1_1") (pintype "passive"))
      (node (ref "L6") (pin "1") (pinfunction "1_1") (pintype "passive"))
      (node (ref "L8") (pin "1") (pinfunction "1_1") (pintype "passive"))
      (node (ref "R40") (pin "2") (pinfunction "2_2") (pintype "bidirectional"))
      (node (ref "R51") (pin "2") (pinfunction "2_2") (pintype "bidirectional"))
      (node (ref "SB1") (pin "2") (pinfunction "B1_2") (pintype "bidirectional"))
      (node (ref "SB1") (pin "2'") (pinfunction "B2_2'") (pintype "bidirectional"))
      (node (ref "SB2") (pin "2") (pinfunction "B1_2") (pintype "bidirectional"))
      (node (ref "SB2") (pin "2'") (pinfunction "B2_2'") (pintype "bidirectional"))
      (node (ref "U12") (pin "3") (pinfunction "VCC_3") (pintype "bidirectional"))
      (node (ref "U13") (pin "1") (pinfunction "VBAT_1") (pintype "bidirectional"))
      (node (ref "U13") (pin "24") (pinfunction "VDD4_24") (pintype "bidirectional"))
      (node (ref "U13") (pin "36") (pinfunction "VDD6_36") (pintype "bidirectional"))
      (node (ref "U13") (pin "48") (pinfunction "VDD8_48") (pintype "bidirectional"))
      (node (ref "U7") (pin "2") (pinfunction "OUT_2") (pintype "output"))
      (node (ref "U7") (pin "4") (pinfunction "OUT_4") (pintype "output"))
    )
    (net (code "2") (name "+5V") (class "Default")
      (node (ref "C28") (pin "1") (pinfunction "1_1") (pintype "passive"))
      (node (ref "C29") (pin "1") (pinfunction "1_1") (pintype "passive"))
      (node (ref "C30") (pin "1") (pinfunction "1_1") (pintype "passive"))
      (node (ref "C31") (pin "1") (pinfunction "1_1") (pintype "passive"))
      (node (ref "C32") (pin "1") (pinfunction "1_1") (pintype "passive"))
      (node (ref "C36") (pin "1") (pinfunction "1_1") (pintype "passive"))
      (node (ref "C38") (pin "1") (pinfunction "1_1") (pintype "passive"))
      (node (ref "C40") (pin "1") (pinfunction "1_1") (pintype "passive"))
      (node (ref "C46") (pin "1") (pinfunction "1_1") (pintype "passive"))
      (node (ref "L2") (pin "2") (pinfunction "2_2") (pintype "passive"))
      (node (ref "L3") (pin "2") (pinfunction "2_2") (pintype "passive"))
      (node (ref "L4") (pin "2") (pinfunction "2_2") (pintype "passive"))
      (node (ref "R6") (pin "2") (pinfunction "2_2") (pintype "bidirectional"))
      (node (ref "R8") (pin "2") (pinfunction "2_2") (pintype "bidirectional"))
      (node (ref "U1") (pin "5") (pinfunction "BIAS_5") (pintype "bidirectional"))
      (node (ref "U2") (pin "1") (pinfunction "VIN_1") (pintype "bidirectional"))
      (node (ref "U2") (pin "3") (pinfunction "ON/~{OFF}_3") (pintype "bidirectional"))
      (node (ref "U3") (pin "3A") (pinfunction "VDD_3A") (pintype "bidirectional"))
      (node (ref "U3") (pin "4C") (pinfunction "VDD_4C") (pintype "bidirectional"))
      (node (ref "U4") (pin "3A") (pinfunction "VDD_3A") (pintype "bidirectional"))
      (node (ref "U4") (pin "4C") (pinfunction "VDD_4C") (pintype "bidirectional"))
      (node (ref "U5") (pin "3A") (pinfunction "VDD_3A") (pintype "bidirectional"))
      (node (ref "U5") (pin "4C") (pinfunction "VDD_4C") (pintype "bidirectional"))
    )
    (net (code "3") (name "3V3_CLAMP") (class "Default")
      (node (ref "C35") (pin "1") (pinfunction "1_1") (pintype "passive"))
      (node (ref "D10") (pin "C") (pinfunction "C_C") (pintype "passive"))
      (node (ref "D14") (pin "C") (pinfunction "C_C") (pintype "passive"))
      (node (ref "D3") (pin "C") (pinfunction "C_C") (pintype "passive"))
      (node (ref "D6") (pin "C") (pinfunction "C_C") (pintype "passive"))
      (node (ref "Q1") (pin "5") (pinfunction "E_5") (pintype "passive"))
      (node (ref "R10") (pin "1") (pinfunction "1_1") (pintype "bidirectional"))
    )
    (net (code "4") (name "3V3_PWR") (class "Default")
      (node (ref "C34") (pin "1") (pinfunction "1_1") (pintype "passive"))
      (node (ref "C42") (pin "1") (pinfunction "1_1") (pintype "passive"))
      (node (ref "Q1") (pin "4") (pinfunction "E_4") (pintype "passive"))
      (node (ref "R10") (pin "2") (pinfunction "2_2") (pintype "bidirectional"))
      (node (ref "R9") (pin "2") (pinfunction "2_2") (pintype "bidirectional"))
      (node (ref "U2") (pin "5") (pinfunction "VOUT_5") (pintype "bidirectional"))
      (node (ref "U6") (pin "4") (pinfunction "VDD_4") (pintype "bidirectional"))
    )
    (net (code "5") (name "BEMF_A") (class "Default")
      (node (ref "D6") (pin "A") (pinfunction "A_A") (pintype "passive"))
      (node (ref "D8") (pin "C") (pinfunction "C_C") (pintype "passive"))
      (node (ref "R20") (pin "2") (pinfunction "2_2") (pintype "bidirectional"))
      (node (ref "R21") (pin "2") (pinfunction "2_2") (pintype "bidirectional"))
      (node (ref "R22") (pin "1") (pinfunction "1_1") (pintype "bidirectional"))
      (node (ref "R50") (pin "1") (pinfunction "1_1") (pintype "bidirectional"))
    )
    (net (code "6") (name "BEMF_B") (class "Default")
      (node (ref "D10") (pin "A") (pinfunction "A_A") (pintype "passive"))
      (node (ref "D12") (pin "C") (pinfunction "C_C") (pintype "passive"))
      (node (ref "R26") (pin "2") (pinfunction "2_2") (pintype "bidirectional"))
      (node (ref "R27") (pin "2") (pinfunction "2_2") (pintype "bidirectional"))
      (node (ref "R28") (pin "1") (pinfunction "1_1") (pintype "bidirectional"))
      (node (ref "R49") (pin "1") (pinfunction "1_1") (pintype "bidirectional"))
    )
    (net (code "7") (name "BEMF_C") (class "Default")
      (node (ref "D14") (pin "A") (pinfunction "A_A") (pintype "passive"))
      (node (ref "D16") (pin "C") (pinfunction "C_C") (pintype "passive"))
      (node (ref "R32") (pin "2") (pinfunction "2_2") (pintype "bidirectional"))
      (node (ref "R33") (pin "2") (pinfunction "2_2") (pintype "bidirectional"))
      (node (ref "R34") (pin "1") (pinfunction "1_1") (pintype "bidirectional"))
      (node (ref "R48") (pin "1") (pinfunction "1_1") (pintype "bidirectional"))
    )
    (net (code "8") (name "CAN_N") (class "Default")
      (node (ref "D18") (pin "1") (pinfunction "P$1_1") (pintype "bidirectional"))
      (node (ref "J5") (pin "4") (pinfunction "4_4") (pintype "bidirectional"))
      (node (ref "R47") (pin "1") (pinfunction "1_1") (pintype "bidirectional"))
      (node (ref "U12") (pin "6") (pinfunction "CANL_6") (pintype "bidirectional"))
    )
    (net (code "9") (name "CAN_P") (class "Default")
      (node (ref "D18") (pin "2") (pinfunction "P$2_2") (pintype "bidirectional"))
      (node (ref "J5") (pin "3") (pinfunction "3_3") (pintype "bidirectional"))
      (node (ref "R47") (pin "2") (pinfunction "2_2") (pintype "bidirectional"))
      (node (ref "U12") (pin "7") (pinfunction "CANH_7") (pintype "bidirectional"))
    )
    (net (code "10") (name "CURRENT_A") (class "Default")
      (node (ref "C61") (pin "1") (pinfunction "1_1") (pintype "passive"))
      (node (ref "R44") (pin "2") (pinfunction "2_2") (pintype "bidirectional"))
      (node (ref "TP48") (pin "P$1") (pinfunction "P$1_P$1") (pintype "bidirectional"))
      (node (ref "U13") (pin "14") (pinfunction "PA6_14") (pintype "bidirectional"))
    )
    (net (code "11") (name "CURRENT_B") (class "Default")
      (node (ref "C66") (pin "1") (pinfunction "1_1") (pintype "passive"))
      (node (ref "R45") (pin "2") (pinfunction "2_2") (pintype "bidirectional"))
      (node (ref "TP47") (pin "P$1") (pinfunction "P$1_P$1") (pintype "bidirectional"))
      (node (ref "U13") (pin "26") (pinfunction "PB12_26") (pintype "bidirectional"))
    )
    (net (code "12") (name "CURRENT_C") (class "Default")
      (node (ref "C71") (pin "1") (pinfunction "1_1") (pintype "passive"))
      (node (ref "R46") (pin "1") (pinfunction "1_1") (pintype "bidirectional"))
      (node (ref "TP58") (pin "P$1") (pinfunction "P$1_P$1") (pintype "bidirectional"))
      (node (ref "U13") (pin "27") (pinfunction "PB13_27") (pintype "bidirectional"))
    )
    (net (code "13") (name "FDCAN1_RX") (class "Default")
      (node (ref "U12") (pin "4") (pinfunction "RXD_4") (pintype "bidirectional"))
      (node (ref "U13") (pin "34") (pinfunction "PA12_34") (pintype "bidirectional"))
    )
    (net (code "14") (name "FDCAN1_TX") (class "Default")
      (node (ref "U12") (pin "1") (pinfunction "TXD_1") (pintype "bidirectional"))
      (node (ref "U13") (pin "33") (pinfunction "PA11_33") (pintype "bidirectional"))
    )
    (net (code "15") (name "FET_A_H") (class "Default")
      (node (ref "TP54") (pin "P$1") (pinfunction "P$1_P$1") (pintype "bidirectional"))
      (node (ref "U13") (pin "30") (pinfunction "PA8_30") (pintype "bidirectional"))
      (node (ref "U3") (pin "4B") (pinfunction "HI_4B") (pintype "bidirectional"))
    )
    (net (code "16") (name "FET_A_L") (class "Default")
      (node (ref "TP57") (pin "P$1") (pinfunction "P$1_P$1") (pintype "bidirectional"))
      (node (ref "U13") (pin "2") (pinfunction "PC13_2") (pintype "bidirectional"))
      (node (ref "U3") (pin "4A") (pinfunction "LI_4A") (pintype "bidirectional"))
    )
    (net (code "17") (name "FET_B_H") (class "Default")
      (node (ref "TP53") (pin "P$1") (pinfunction "P$1_P$1") (pintype "bidirectional"))
      (node (ref "U13") (pin "31") (pinfunction "PA9_31") (pintype "bidirectional"))
      (node (ref "U4") (pin "4B") (pinfunction "HI_4B") (pintype "bidirectional"))
    )
    (net (code "18") (name "FET_B_L") (class "Default")
      (node (ref "TP56") (pin "P$1") (pinfunction "P$1_P$1") (pintype "bidirectional"))
      (node (ref "U13") (pin "28") (pinfunction "PB14_28") (pintype "bidirectional"))
      (node (ref "U4") (pin "4A") (pinfunction "LI_4A") (pintype "bidirectional"))
    )
    (net (code "19") (name "FET_C_H") (class "Default")
      (node (ref "TP52") (pin "P$1") (pinfunction "P$1_P$1") (pintype "bidirectional"))
      (node (ref "U13") (pin "32") (pinfunction "PA10_32") (pintype "bidirectional"))
      (node (ref "U5") (pin "4B") (pinfunction "HI_4B") (pintype "bidirectional"))
    )
    (net (code "20") (name "FET_C_L") (class "Default")
      (node (ref "TP55") (pin "P$1") (pinfunction "P$1_P$1") (pintype "bidirectional"))
      (node (ref "U13") (pin "29") (pinfunction "PB15_29") (pintype "bidirectional"))
      (node (ref "U5") (pin "4A") (pinfunction "LI_4A") (pintype "bidirectional"))
    )
    (net (code "21") (name "FET_TEMP_SENSE") (class "Default")
      (node (ref "C43") (pin "1") (pinfunction "1_1") (pintype "passive"))
      (node (ref "R54") (pin "1") (pinfunction "1_1") (pintype "bidirectional"))
      (node (ref "U6") (pin "3") (pinfunction "VOUT_3") (pintype "bidirectional"))
    )
    (net (code "22") (name "GND") (class "Default")
      (node (ref "BRIDGE1") (pin "2") (pinfunction "2_2") (pintype "bidirectional"))
      (node (ref "C1") (pin "-") (pinfunction "-_-") (pintype "passive"))
      (node (ref "C10") (pin "2") (pinfunction "2_2") (pintype "passive"))
      (node (ref "C11") (pin "2") (pinfunction "2_2") (pintype "passive"))
      (node (ref "C12") (pin "2") (pinfunction "2_2") (pintype "passive"))
      (node (ref "C13") (pin "2") (pinfunction "2_2") (pintype "passive"))
      (node (ref "C14") (pin "2") (pinfunction "2_2") (pintype "passive"))
      (node (ref "C15") (pin "2") (pinfunction "2_2") (pintype "passive"))
      (node (ref "C16") (pin "2") (pinfunction "2_2") (pintype "passive"))
      (node (ref "C17") (pin "2") (pinfunction "2_2") (pintype "passive"))
      (node (ref "C18") (pin "2") (pinfunction "2_2") (pintype "passive"))
      (node (ref "C19") (pin "2") (pinfunction "2_2") (pintype "passive"))
      (node (ref "C2") (pin "-") (pinfunction "-_-") (pintype "passive"))
      (node (ref "C20") (pin "2") (pinfunction "2_2") (pintype "passive"))
      (node (ref "C21") (pin "2") (pinfunction "2_2") (pintype "passive"))
      (node (ref "C22") (pin "2") (pinfunction "2_2") (pintype "passive"))
      (node (ref "C23") (pin "2") (pinfunction "2_2") (pintype "passive"))
      (node (ref "C24") (pin "2") (pinfunction "2_2") (pintype "passive"))
      (node (ref "C25") (pin "2") (pinfunction "2_2") (pintype "passive"))
      (node (ref "C27") (pin "2") (pinfunction "2_2") (pintype "passive"))
      (node (ref "C28") (pin "2") (pinfunction "2_2") (pintype "passive"))
      (node (ref "C3") (pin "-") (pinfunction "-_-") (pintype "passive"))
      (node (ref "C30") (pin "2") (pinfunction "2_2") (pintype "passive"))
      (node (ref "C31") (pin "2") (pinfunction "2_2") (pintype "passive"))
      (node (ref "C32") (pin "2") (pinfunction "2_2") (pintype "passive"))
      (node (ref "C33") (pin "2") (pinfunction "2_2") (pintype "passive"))
      (node (ref "C34") (pin "2") (pinfunction "2_2") (pintype "passive"))
      (node (ref "C35") (pin "2") (pinfunction "2_2") (pintype "passive"))
      (node (ref "C36") (pin "2") (pinfunction "2_2") (pintype "passive"))
      (node (ref "C38") (pin "2") (pinfunction "2_2") (pintype "passive"))
      (node (ref "C4") (pin "2") (pinfunction "2_2") (pintype "passive"))
      (node (ref "C40") (pin "2") (pinfunction "2_2") (pintype "passive"))
      (node (ref "C42") (pin "2") (pinfunction "2_2") (pintype "passive"))
      (node (ref "C43") (pin "2") (pinfunction "2_2") (pintype "passive"))
      (node (ref "C5") (pin "2") (pinfunction "2_2") (pintype "passive"))
      (node (ref "C6") (pin "2") (pinfunction "2_2") (pintype "passive"))
      (node (ref "C7") (pin "2") (pinfunction "2_2") (pintype "passive"))
      (node (ref "C8") (pin "2") (pinfunction "2_2") (pintype "passive"))
      (node (ref "C9") (pin "2") (pinfunction "2_2") (pintype "passive"))
      (node (ref "D1") (pin "A") (pinfunction "A_A") (pintype "passive"))
      (node (ref "D12") (pin "A") (pinfunction "A_A") (pintype "passive"))
      (node (ref "D13") (pin "A") (pinfunction "A_A") (pintype "passive"))
      (node (ref "D16") (pin "A") (pinfunction "A_A") (pintype "passive"))
      (node (ref "D18") (pin "3") (pinfunction "P$3_3") (pintype "bidirectional"))
      (node (ref "D19") (pin "A") (pinfunction "A_A") (pintype "passive"))
      (node (ref "D4") (pin "A") (pinfunction "A_A") (pintype "passive"))
      (node (ref "D5") (pin "A") (pinfunction "A_A") (pintype "passive"))
      (node (ref "D8") (pin "A") (pinfunction "A_A") (pintype "passive"))
      (node (ref "D9") (pin "A") (pinfunction "A_A") (pintype "passive"))
      (node (ref "J1") (pin "1") (pinfunction "1_1") (pintype "bidirectional"))
      (node (ref "J1") (pin "3") (pinfunction "3_3") (pintype "bidirectional"))
      (node (ref "J1") (pin "4") (pinfunction "4_4") (pintype "bidirectional"))
      (node (ref "J5") (pin "2") (pinfunction "2_2") (pintype "bidirectional"))
      (node (ref "J5") (pin "5") (pinfunction "P$1_5") (pintype "bidirectional"))
      (node (ref "J5") (pin "6") (pinfunction "P$1_6") (pintype "bidirectional"))
      (node (ref "J5") (pin "7") (pinfunction "P$2_7") (pintype "bidirectional"))
      (node (ref "J5") (pin "8") (pinfunction "P$2_8") (pintype "bidirectional"))
      (node (ref "LED1") (pin "C") (pinfunction "C_C") (pintype "passive"))
      (node (ref "LED2") (pin "C") (pinfunction "C_C") (pintype "passive"))
      (node (ref "Q1") (pin "6") (pinfunction "C_6") (pintype "passive"))
      (node (ref "Q5") (pin "10") (pinfunction "S_10") (pintype "passive"))
      (node (ref "Q5") (pin "13") (pinfunction "S_13") (pintype "passive"))
      (node (ref "Q5") (pin "14") (pinfunction "S_14") (pintype "passive"))
      (node (ref "Q5") (pin "17") (pinfunction "S_17") (pintype "passive"))
      (node (ref "Q5") (pin "18") (pinfunction "S_18") (pintype "passive"))
      (node (ref "Q5") (pin "2") (pinfunction "S_2") (pintype "passive"))
      (node (ref "Q5") (pin "21") (pinfunction "S_21") (pintype "passive"))
      (node (ref "Q5") (pin "22") (pinfunction "S_22") (pintype "passive"))
      (node (ref "Q5") (pin "25") (pinfunction "S_25") (pintype "passive"))
      (node (ref "Q5") (pin "26") (pinfunction "S_26") (pintype "passive"))
      (node (ref "Q5") (pin "29") (pinfunction "S_29") (pintype "passive"))
      (node (ref "Q5") (pin "30") (pinfunction "S_30") (pintype "passive"))
      (node (ref "Q5") (pin "5") (pinfunction "S_5") (pintype "passive"))
      (node (ref "Q5") (pin "6") (pinfunction "S_6") (pintype "passive"))
      (node (ref "Q5") (pin "9") (pinfunction "S_9") (pintype "passive"))
      (node (ref "Q7") (pin "10") (pinfunction "S_10") (pintype "passive"))
      (node (ref "Q7") (pin "13") (pinfunction "S_13") (pintype "passive"))
      (node (ref "Q7") (pin "14") (pinfunction "S_14") (pintype "passive"))
      (node (ref "Q7") (pin "17") (pinfunction "S_17") (pintype "passive"))
      (node (ref "Q7") (pin "18") (pinfunction "S_18") (pintype "passive"))
      (node (ref "Q7") (pin "2") (pinfunction "S_2") (pintype "passive"))
      (node (ref "Q7") (pin "21") (pinfunction "S_21") (pintype "passive"))
      (node (ref "Q7") (pin "22") (pinfunction "S_22") (pintype "passive"))
      (node (ref "Q7") (pin "25") (pinfunction "S_25") (pintype "passive"))
      (node (ref "Q7") (pin "26") (pinfunction "S_26") (pintype "passive"))
      (node (ref "Q7") (pin "29") (pinfunction "S_29") (pintype "passive"))
      (node (ref "Q7") (pin "30") (pinfunction "S_30") (pintype "passive"))
      (node (ref "Q7") (pin "5") (pinfunction "S_5") (pintype "passive"))
      (node (ref "Q7") (pin "6") (pinfunction "S_6") (pintype "passive"))
      (node (ref "Q7") (pin "9") (pinfunction "S_9") (pintype "passive"))
      (node (ref "Q9") (pin "10") (pinfunction "S_10") (pintype "passive"))
      (node (ref "Q9") (pin "13") (pinfunction "S_13") (pintype "passive"))
      (node (ref "Q9") (pin "14") (pinfunction "S_14") (pintype "passive"))
      (node (ref "Q9") (pin "17") (pinfunction "S_17") (pintype "passive"))
      (node (ref "Q9") (pin "18") (pinfunction "S_18") (pintype "passive"))
      (node (ref "Q9") (pin "2") (pinfunction "S_2") (pintype "passive"))
      (node (ref "Q9") (pin "21") (pinfunction "S_21") (pintype "passive"))
      (node (ref "Q9") (pin "22") (pinfunction "S_22") (pintype "passive"))
      (node (ref "Q9") (pin "25") (pinfunction "S_25") (pintype "passive"))
      (node (ref "Q9") (pin "26") (pinfunction "S_26") (pintype "passive"))
      (node (ref "Q9") (pin "29") (pinfunction "S_29") (pintype "passive"))
      (node (ref "Q9") (pin "30") (pinfunction "S_30") (pintype "passive"))
      (node (ref "Q9") (pin "5") (pinfunction "S_5") (pintype "passive"))
      (node (ref "Q9") (pin "6") (pinfunction "S_6") (pintype "passive"))
      (node (ref "Q9") (pin "9") (pinfunction "S_9") (pintype "passive"))
      (node (ref "R11") (pin "1") (pinfunction "1_1") (pintype "bidirectional"))
      (node (ref "R14") (pin "1") (pinfunction "1_1") (pintype "bidirectional"))
      (node (ref "R16") (pin "1") (pinfunction "1_1") (pintype "bidirectional"))
      (node (ref "R21") (pin "1") (pinfunction "1_1") (pintype "bidirectional"))
      (node (ref "R27") (pin "1") (pinfunction "1_1") (pintype "bidirectional"))
      (node (ref "R33") (pin "1") (pinfunction "1_1") (pintype "bidirectional"))
      (node (ref "R4") (pin "1") (pinfunction "1_1") (pintype "bidirectional"))
      (node (ref "R5") (pin "1") (pinfunction "1_1") (pintype "bidirectional"))
      (node (ref "R7") (pin "1") (pinfunction "1_1") (pintype "bidirectional"))
      (node (ref "TP1") (pin "P$1") (pinfunction "P$1_P$1") (pintype "bidirectional"))
      (node (ref "TP10") (pin "P$1") (pinfunction "P$1_P$1") (pintype "bidirectional"))
      (node (ref "TP11") (pin "P$1") (pinfunction "P$1_P$1") (pintype "bidirectional"))
      (node (ref "TP12") (pin "P$1") (pinfunction "P$1_P$1") (pintype "bidirectional"))
      (node (ref "TP13") (pin "P$1") (pinfunction "P$1_P$1") (pintype "bidirectional"))
      (node (ref "TP14") (pin "P$1") (pinfunction "P$1_P$1") (pintype "bidirectional"))
      (node (ref "TP15") (pin "P$1") (pinfunction "P$1_P$1") (pintype "bidirectional"))
      (node (ref "TP16") (pin "P$1") (pinfunction "P$1_P$1") (pintype "bidirectional"))
      (node (ref "TP2") (pin "P$1") (pinfunction "P$1_P$1") (pintype "bidirectional"))
      (node (ref "TP3") (pin "P$1") (pinfunction "P$1_P$1") (pintype "bidirectional"))
      (node (ref "TP4") (pin "P$1") (pinfunction "P$1_P$1") (pintype "bidirectional"))
      (node (ref "TP5") (pin "P$1") (pinfunction "P$1_P$1") (pintype "bidirectional"))
      (node (ref "TP6") (pin "P$1") (pinfunction "P$1_P$1") (pintype "bidirectional"))
      (node (ref "TP7") (pin "P$1") (pinfunction "P$1_P$1") (pintype "bidirectional"))
      (node (ref "TP8") (pin "P$1") (pinfunction "P$1_P$1") (pintype "bidirectional"))
      (node (ref "TP9") (pin "P$1") (pinfunction "P$1_P$1") (pintype "bidirectional"))
      (node (ref "U1") (pin "10") (pinfunction "AGND_10") (pintype "bidirectional"))
      (node (ref "U1") (pin "15") (pinfunction "PGND_15") (pintype "bidirectional"))
      (node (ref "U1") (pin "16") (pinfunction "PGND_16") (pintype "bidirectional"))
      (node (ref "U1") (pin "6") (pinfunction "SYNC_6") (pintype "bidirectional"))
      (node (ref "U1") (pin "PAD") (pinfunction "PGND_PAD") (pintype "bidirectional"))
      (node (ref "U2") (pin "2") (pinfunction "GND_2") (pintype "bidirectional"))
      (node (ref "U3") (pin "2A") (pinfunction "VSS_2A") (pintype "bidirectional"))
      (node (ref "U4") (pin "2A") (pinfunction "VSS_2A") (pintype "bidirectional"))
      (node (ref "U5") (pin "2A") (pinfunction "VSS_2A") (pintype "bidirectional"))
      (node (ref "U6") (pin "1") (pinfunction "GND_1") (pintype "bidirectional"))
      (node (ref "U6") (pin "2") (pinfunction "GND_2") (pintype "bidirectional"))
      (node (ref "U6") (pin "5") (pinfunction "GND_5") (pintype "bidirectional"))
    )
    (net (code "23") (name "GND1") (class "Default")
      (node (ref "BRIDGE1") (pin "1") (pinfunction "1_1") (pintype "bidirectional"))
      (node (ref "C44") (pin "2") (pinfunction "2_2") (pintype "passive"))
      (node (ref "C45") (pin "2") (pinfunction "2_2") (pintype "passive"))
      (node (ref "C46") (pin "2") (pinfunction "2_2") (pintype "passive"))
      (node (ref "C47") (pin "2") (pinfunction "2_2") (pintype "passive"))
      (node (ref "C48") (pin "2") (pinfunction "2_2") (pintype "passive"))
      (node (ref "C49") (pin "2") (pinfunction "2_2") (pintype "passive"))
      (node (ref "C50") (pin "2") (pinfunction "2_2") (pintype "passive"))
      (node (ref "C51") (pin "2") (pinfunction "2_2") (pintype "passive"))
      (node (ref "C52") (pin "2") (pinfunction "2_2") (pintype "passive"))
      (node (ref "C53") (pin "2") (pinfunction "2_2") (pintype "passive"))
      (node (ref "C55") (pin "2") (pinfunction "2_2") (pintype "passive"))
      (node (ref "C56") (pin "2") (pinfunction "2_2") (pintype "passive"))
      (node (ref "C57") (pin "2") (pinfunction "2_2") (pintype "passive"))
      (node (ref "C58") (pin "2") (pinfunction "2_2") (pintype "passive"))
      (node (ref "C59") (pin "2") (pinfunction "2_2") (pintype "passive"))
      (node (ref "C60") (pin "2") (pinfunction "2_2") (pintype "passive"))
      (node (ref "C61") (pin "2") (pinfunction "2_2") (pintype "passive"))
      (node (ref "C62") (pin "2") (pinfunction "2_2") (pintype "passive"))
      (node (ref "C63") (pin "2") (pinfunction "2_2") (pintype "passive"))
      (node (ref "C64") (pin "2") (pinfunction "2_2") (pintype "passive"))
      (node (ref "C65") (pin "2") (pinfunction "2_2") (pintype "passive"))
      (node (ref "C66") (pin "2") (pinfunction "2_2") (pintype "passive"))
      (node (ref "C67") (pin "2") (pinfunction "2_2") (pintype "passive"))
      (node (ref "C68") (pin "2") (pinfunction "2_2") (pintype "passive"))
      (node (ref "C69") (pin "2") (pinfunction "2_2") (pintype "passive"))
      (node (ref "C70") (pin "2") (pinfunction "2_2") (pintype "passive"))
      (node (ref "C71") (pin "2") (pinfunction "2_2") (pintype "passive"))
      (node (ref "C72") (pin "2") (pinfunction "2_2") (pintype "passive"))
      (node (ref "C73") (pin "2") (pinfunction "2_2") (pintype "passive"))
      (node (ref "C74") (pin "2") (pinfunction "2_2") (pintype "passive"))
      (node (ref "C75") (pin "2") (pinfunction "2_2") (pintype "passive"))
      (node (ref "C76") (pin "2") (pinfunction "2_2") (pintype "passive"))
      (node (ref "C77") (pin "2") (pinfunction "2_2") (pintype "passive"))
      (node (ref "C78") (pin "1") (pinfunction "1_1") (pintype "passive"))
      (node (ref "C79") (pin "1") (pinfunction "1_1") (pintype "passive"))
      (node (ref "C80") (pin "2") (pinfunction "2_2") (pintype "passive"))
      (node (ref "C81") (pin "2") (pinfunction "2_2") (pintype "passive"))
      (node (ref "C82") (pin "2") (pinfunction "2_2") (pintype "passive"))
      (node (ref "C83") (pin "2") (pinfunction "2_2") (pintype "passive"))
      (node (ref "C84") (pin "2") (pinfunction "2_2") (pintype "passive"))
      (node (ref "C85") (pin "2") (pinfunction "2_2") (pintype "passive"))
      (node (ref "C86") (pin "2") (pinfunction "2_2") (pintype "passive"))
      (node (ref "C87") (pin "2") (pinfunction "2_2") (pintype "passive"))
      (node (ref "C88") (pin "2") (pinfunction "2_2") (pintype "passive"))
      (node (ref "C89") (pin "2") (pinfunction "2_2") (pintype "passive"))
      (node (ref "D17") (pin "A") (pinfunction "A_A") (pintype "passive"))
      (node (ref "D20") (pin "A") (pinfunction "A_A") (pintype "passive"))
      (node (ref "D21") (pin "2") (pinfunction "2_2") (pintype "passive"))
      (node (ref "D22") (pin "2") (pinfunction "2_2") (pintype "passive"))
      (node (ref "J6") (pin "11") (pinfunction "11_11") (pintype "bidirectional"))
      (node (ref "J6") (pin "5") (pinfunction "5_5") (pintype "bidirectional"))
      (node (ref "J6") (pin "7") (pinfunction "7_7") (pintype "bidirectional"))
      (node (ref "LED3") (pin "C") (pinfunction "C_C") (pintype "passive"))
      (node (ref "LED4") (pin "C") (pinfunction "C_C") (pintype "passive"))
      (node (ref "LED5") (pin "C") (pinfunction "C_C") (pintype "passive"))
      (node (ref "LED6") (pin "C") (pinfunction "C_C") (pintype "passive"))
      (node (ref "LED7") (pin "C") (pinfunction "C_C") (pintype "passive"))
      (node (ref "R36") (pin "1") (pinfunction "1_1") (pintype "bidirectional"))
      (node (ref "R38") (pin "1") (pinfunction "1_1") (pintype "bidirectional"))
      (node (ref "R43") (pin "1") (pinfunction "1_1") (pintype "bidirectional"))
      (node (ref "R53") (pin "1") (pinfunction "1_1") (pintype "bidirectional"))
      (node (ref "TP27") (pin "P$1") (pinfunction "P$1_P$1") (pintype "bidirectional"))
      (node (ref "TP28") (pin "P$1") (pinfunction "P$1_P$1") (pintype "bidirectional"))
      (node (ref "TP29") (pin "P$1") (pinfunction "P$1_P$1") (pintype "bidirectional"))
      (node (ref "TP30") (pin "P$1") (pinfunction "P$1_P$1") (pintype "bidirectional"))
      (node (ref "TP31") (pin "P$1") (pinfunction "P$1_P$1") (pintype "bidirectional"))
      (node (ref "TP32") (pin "P$1") (pinfunction "P$1_P$1") (pintype "bidirectional"))
      (node (ref "TP33") (pin "P$1") (pinfunction "P$1_P$1") (pintype "bidirectional"))
      (node (ref "TP34") (pin "P$1") (pinfunction "P$1_P$1") (pintype "bidirectional"))
      (node (ref "TP35") (pin "P$1") (pinfunction "P$1_P$1") (pintype "bidirectional"))
      (node (ref "TP36") (pin "P$1") (pinfunction "P$1_P$1") (pintype "bidirectional"))
      (node (ref "TP37") (pin "P$1") (pinfunction "P$1_P$1") (pintype "bidirectional"))
      (node (ref "TP38") (pin "P$1") (pinfunction "P$1_P$1") (pintype "bidirectional"))
      (node (ref "TP39") (pin "P$1") (pinfunction "P$1_P$1") (pintype "bidirectional"))
      (node (ref "TP40") (pin "P$1") (pinfunction "P$1_P$1") (pintype "bidirectional"))
      (node (ref "TP41") (pin "P$1") (pinfunction "P$1_P$1") (pintype "bidirectional"))
      (node (ref "TP60") (pin "P$1") (pinfunction "P$1_P$1") (pintype "bidirectional"))
      (node (ref "U10") (pin "2") (pinfunction "GND_2") (pintype "bidirectional"))
      (node (ref "U10") (pin "4") (pinfunction "NC_4") (pintype "bidirectional"))
      (node (ref "U10") (pin "7") (pinfunction "REF1_7") (pintype "bidirectional"))
      (node (ref "U11") (pin "2") (pinfunction "GND_2") (pintype "bidirectional"))
      (node (ref "U11") (pin "4") (pinfunction "NC_4") (pintype "bidirectional"))
      (node (ref "U11") (pin "7") (pinfunction "REF1_7") (pintype "bidirectional"))
      (node (ref "U12") (pin "2") (pinfunction "GND_2") (pintype "bidirectional"))
      (node (ref "U12") (pin "8") (pinfunction "RS/NC_8") (pintype "bidirectional"))
      (node (ref "U13") (pin "19") (pinfunction "VSSA_19") (pintype "bidirectional"))
      (node (ref "U13") (pin "23") (pinfunction "VSS4_23") (pintype "bidirectional"))
      (node (ref "U13") (pin "35") (pinfunction "VSS6_35") (pintype "bidirectional"))
      (node (ref "U13") (pin "47") (pinfunction "VSS8_47") (pintype "bidirectional"))
      (node (ref "U7") (pin "1") (pinfunction "GND/ADJ_1") (pintype "passive"))
      (node (ref "U8") (pin "3") (pinfunction "A_3") (pintype "passive"))
      (node (ref "U9") (pin "2") (pinfunction "GND_2") (pintype "bidirectional"))
      (node (ref "U9") (pin "4") (pinfunction "NC_4") (pintype "bidirectional"))
      (node (ref "U9") (pin "7") (pinfunction "REF1_7") (pintype "bidirectional"))
      (node (ref "Y1") (pin "2") (pinfunction "3_2") (pintype "passive"))
      (node (ref "Y1") (pin "4") (pinfunction "3_4") (pintype "passive"))
    )
    (net (code "24") (name "GPIO_BEMF") (class "Default")
      (node (ref "D11") (pin "C") (pinfunction "C_C") (pintype "passive"))
      (node (ref "D15") (pin "C") (pinfunction "C_C") (pintype "passive"))
      (node (ref "D7") (pin "C") (pinfunction "C_C") (pintype "passive"))
      (node (ref "TP50") (pin "P$1") (pinfunction "P$1_P$1") (pintype "bidirectional"))
      (node (ref "U13") (pin "12") (pinfunction "PA4_12") (pintype "bidirectional"))
    )
    (net (code "25") (name "JTCK{slash}SWCLK") (class "Default")
      (node (ref "D22") (pin "1") (pinfunction "1_1") (pintype "passive"))
      (node (ref "J6") (pin "6") (pinfunction "6_6") (pintype "bidirectional"))
      (node (ref "J6") (pin "9") (pinfunction "9_9") (pintype "bidirectional"))
      (node (ref "U13") (pin "38") (pinfunction "PA14_38") (pintype "bidirectional"))
    )
    (net (code "26") (name "JTDI") (class "Default")
      (node (ref "D22") (pin "3") (pinfunction "3_3") (pintype "passive"))
      (node (ref "J6") (pin "10") (pinfunction "10_10") (pintype "bidirectional"))
      (node (ref "U13") (pin "39") (pinfunction "PA15_39") (pintype "bidirectional"))
    )
    (net (code "27") (name "JTDO{slash}SWO") (class "Default")
      (node (ref "D21") (pin "6") (pinfunction "6_6") (pintype "passive"))
      (node (ref "J6") (pin "8") (pinfunction "8_8") (pintype "bidirectional"))
      (node (ref "U13") (pin "40") (pinfunction "PB3_40") (pintype "bidirectional"))
    )
    (net (code "28") (name "JTMS{slash}SWDIO") (class "Default")
      (node (ref "D21") (pin "5") (pinfunction "5_5") (pintype "passive"))
      (node (ref "J6") (pin "4") (pinfunction "4_4") (pintype "bidirectional"))
      (node (ref "U13") (pin "37") (pinfunction "PA13_37") (pintype "bidirectional"))
    )
    (net (code "29") (name "LED1") (class "Default")
      (node (ref "R55") (pin "2") (pinfunction "2_2") (pintype "bidirectional"))
      (node (ref "U13") (pin "46") (pinfunction "PB9_46") (pintype "bidirectional"))
    )
    (net (code "30") (name "LED2") (class "Default")
      (node (ref "R56") (pin "2") (pinfunction "2_2") (pintype "bidirectional"))
      (node (ref "U13") (pin "42") (pinfunction "PB5_42") (pintype "bidirectional"))
    )
    (net (code "31") (name "LED3") (class "Default")
      (node (ref "R57") (pin "2") (pinfunction "2_2") (pintype "bidirectional"))
      (node (ref "U13") (pin "13") (pinfunction "PA5_13") (pintype "bidirectional"))
    )
    (net (code "32") (name "LED4") (class "Default")
      (node (ref "R58") (pin "2") (pinfunction "2_2") (pintype "bidirectional"))
      (node (ref "U13") (pin "22") (pinfunction "PB10_22") (pintype "bidirectional"))
    )
    (net (code "33") (name "MEASURE_VIN") (class "Default")
      (node (ref "R12") (pin "1") (pinfunction "1_1") (pintype "bidirectional"))
      (node (ref "U13") (pin "15") (pinfunction "PA7_15") (pintype "bidirectional"))
    )
    (net (code "34") (name "MOTOR_TEMP_SENSE") (class "Default")
      (node (ref "C84") (pin "1") (pinfunction "1_1") (pintype "passive"))
      (node (ref "R52") (pin "2") (pinfunction "2_2") (pintype "bidirectional"))
      (node (ref "U13") (pin "16") (pinfunction "PB0_16") (pintype "bidirectional"))
    )
    (net (code "35") (name "Net-(C23-Pad1)") (class "Default")
      (node (ref "C23") (pin "1") (pinfunction "1_1") (pintype "passive"))
      (node (ref "L1") (pin "1") (pinfunction "1_1") (pintype "passive"))
      (node (ref "R1") (pin "2") (pinfunction "2_2") (pintype "bidirectional"))
      (node (ref "R2") (pin "2") (pinfunction "2_2") (pintype "bidirectional"))
    )
    (net (code "36") (name "Net-(C24-Pad1)") (class "Default")
      (node (ref "C24") (pin "1") (pinfunction "1_1") (pintype "passive"))
      (node (ref "L1") (pin "2") (pinfunction "2_2") (pintype "passive"))
      (node (ref "R3") (pin "2") (pinfunction "2_2") (pintype "bidirectional"))
      (node (ref "U1") (pin "13") (pinfunction "VIN_13") (pintype "bidirectional"))
      (node (ref "U1") (pin "14") (pinfunction "VIN_14") (pintype "bidirectional"))
    )
    (net (code "37") (name "Net-(C26-Pad1)") (class "Default")
      (node (ref "C26") (pin "1") (pinfunction "1_1") (pintype "passive"))
      (node (ref "L2") (pin "1") (pinfunction "1_1") (pintype "passive"))
      (node (ref "U1") (pin "1") (pinfunction "SW_1") (pintype "bidirectional"))
      (node (ref "U1") (pin "2") (pinfunction "SW_2") (pintype "bidirectional"))
    )
    (net (code "38") (name "Net-(C37-Pad2)") (class "Default")
      (node (ref "C37") (pin "2") (pinfunction "2_2") (pintype "passive"))
      (node (ref "Q4") (pin "10") (pinfunction "S_10") (pintype "passive"))
      (node (ref "Q4") (pin "13") (pinfunction "S_13") (pintype "passive"))
      (node (ref "Q4") (pin "14") (pinfunction "S_14") (pintype "passive"))
      (node (ref "Q4") (pin "17") (pinfunction "S_17") (pintype "passive"))
      (node (ref "Q4") (pin "18") (pinfunction "S_18") (pintype "passive"))
      (node (ref "Q4") (pin "2") (pinfunction "S_2") (pintype "passive"))
      (node (ref "Q4") (pin "21") (pinfunction "S_21") (pintype "passive"))
      (node (ref "Q4") (pin "22") (pinfunction "S_22") (pintype "passive"))
      (node (ref "Q4") (pin "25") (pinfunction "S_25") (pintype "passive"))
      (node (ref "Q4") (pin "26") (pinfunction "S_26") (pintype "passive"))
      (node (ref "Q4") (pin "29") (pinfunction "S_29") (pintype "passive"))
      (node (ref "Q4") (pin "30") (pinfunction "S_30") (pintype "passive"))
      (node (ref "Q4") (pin "5") (pinfunction "S_5") (pintype "passive"))
      (node (ref "Q4") (pin "6") (pinfunction "S_6") (pintype "passive"))
      (node (ref "Q4") (pin "9") (pinfunction "S_9") (pintype "passive"))
      (node (ref "Q5") (pin "11") (pinfunction "D_11") (pintype "passive"))
      (node (ref "Q5") (pin "12") (pinfunction "D_12") (pintype "passive"))
      (node (ref "Q5") (pin "15") (pinfunction "D_15") (pintype "passive"))
      (node (ref "Q5") (pin "16") (pinfunction "D_16") (pintype "passive"))
      (node (ref "Q5") (pin "19") (pinfunction "D_19") (pintype "passive"))
      (node (ref "Q5") (pin "20") (pinfunction "D_20") (pintype "passive"))
      (node (ref "Q5") (pin "23") (pinfunction "D_23") (pintype "passive"))
      (node (ref "Q5") (pin "24") (pinfunction "D_24") (pintype "passive"))
      (node (ref "Q5") (pin "27") (pinfunction "D_27") (pintype "passive"))
      (node (ref "Q5") (pin "28") (pinfunction "D_28") (pintype "passive"))
      (node (ref "Q5") (pin "3") (pinfunction "D_3") (pintype "passive"))
      (node (ref "Q5") (pin "4") (pinfunction "D_4") (pintype "passive"))
      (node (ref "Q5") (pin "7") (pinfunction "D_7") (pintype "passive"))
      (node (ref "Q5") (pin "8") (pinfunction "D_8") (pintype "passive"))
      (node (ref "R19") (pin "1") (pinfunction "1_1") (pintype "passive"))
      (node (ref "R19") (pin "3") (pinfunction "1_3") (pintype "passive"))
      (node (ref "TP20") (pin "P$1") (pinfunction "P$1_P$1") (pintype "bidirectional"))
      (node (ref "U3") (pin "1C") (pinfunction "HS_1C") (pintype "bidirectional"))
      (node (ref "U3") (pin "4D") (pinfunction "HS_4D") (pintype "bidirectional"))
    )
    (net (code "39") (name "Net-(C39-Pad2)") (class "Default")
      (node (ref "C39") (pin "2") (pinfunction "2_2") (pintype "passive"))
      (node (ref "Q6") (pin "10") (pinfunction "S_10") (pintype "passive"))
      (node (ref "Q6") (pin "13") (pinfunction "S_13") (pintype "passive"))
      (node (ref "Q6") (pin "14") (pinfunction "S_14") (pintype "passive"))
      (node (ref "Q6") (pin "17") (pinfunction "S_17") (pintype "passive"))
      (node (ref "Q6") (pin "18") (pinfunction "S_18") (pintype "passive"))
      (node (ref "Q6") (pin "2") (pinfunction "S_2") (pintype "passive"))
      (node (ref "Q6") (pin "21") (pinfunction "S_21") (pintype "passive"))
      (node (ref "Q6") (pin "22") (pinfunction "S_22") (pintype "passive"))
      (node (ref "Q6") (pin "25") (pinfunction "S_25") (pintype "passive"))
      (node (ref "Q6") (pin "26") (pinfunction "S_26") (pintype "passive"))
      (node (ref "Q6") (pin "29") (pinfunction "S_29") (pintype "passive"))
      (node (ref "Q6") (pin "30") (pinfunction "S_30") (pintype "passive"))
      (node (ref "Q6") (pin "5") (pinfunction "S_5") (pintype "passive"))
      (node (ref "Q6") (pin "6") (pinfunction "S_6") (pintype "passive"))
      (node (ref "Q6") (pin "9") (pinfunction "S_9") (pintype "passive"))
      (node (ref "Q7") (pin "11") (pinfunction "D_11") (pintype "passive"))
      (node (ref "Q7") (pin "12") (pinfunction "D_12") (pintype "passive"))
      (node (ref "Q7") (pin "15") (pinfunction "D_15") (pintype "passive"))
      (node (ref "Q7") (pin "16") (pinfunction "D_16") (pintype "passive"))
      (node (ref "Q7") (pin "19") (pinfunction "D_19") (pintype "passive"))
      (node (ref "Q7") (pin "20") (pinfunction "D_20") (pintype "passive"))
      (node (ref "Q7") (pin "23") (pinfunction "D_23") (pintype "passive"))
      (node (ref "Q7") (pin "24") (pinfunction "D_24") (pintype "passive"))
      (node (ref "Q7") (pin "27") (pinfunction "D_27") (pintype "passive"))
      (node (ref "Q7") (pin "28") (pinfunction "D_28") (pintype "passive"))
      (node (ref "Q7") (pin "3") (pinfunction "D_3") (pintype "passive"))
      (node (ref "Q7") (pin "4") (pinfunction "D_4") (pintype "passive"))
      (node (ref "Q7") (pin "7") (pinfunction "D_7") (pintype "passive"))
      (node (ref "Q7") (pin "8") (pinfunction "D_8") (pintype "passive"))
      (node (ref "R25") (pin "1") (pinfunction "1_1") (pintype "passive"))
      (node (ref "R25") (pin "3") (pinfunction "1_3") (pintype "passive"))
      (node (ref "TP23") (pin "P$1") (pinfunction "P$1_P$1") (pintype "bidirectional"))
      (node (ref "U4") (pin "1C") (pinfunction "HS_1C") (pintype "bidirectional"))
      (node (ref "U4") (pin "4D") (pinfunction "HS_4D") (pintype "bidirectional"))
    )
    (net (code "40") (name "Net-(C41-Pad2)") (class "Default")
      (node (ref "C41") (pin "2") (pinfunction "2_2") (pintype "passive"))
      (node (ref "Q8") (pin "10") (pinfunction "S_10") (pintype "passive"))
      (node (ref "Q8") (pin "13") (pinfunction "S_13") (pintype "passive"))
      (node (ref "Q8") (pin "14") (pinfunction "S_14") (pintype "passive"))
      (node (ref "Q8") (pin "17") (pinfunction "S_17") (pintype "passive"))
      (node (ref "Q8") (pin "18") (pinfunction "S_18") (pintype "passive"))
      (node (ref "Q8") (pin "2") (pinfunction "S_2") (pintype "passive"))
      (node (ref "Q8") (pin "21") (pinfunction "S_21") (pintype "passive"))
      (node (ref "Q8") (pin "22") (pinfunction "S_22") (pintype "passive"))
      (node (ref "Q8") (pin "25") (pinfunction "S_25") (pintype "passive"))
      (node (ref "Q8") (pin "26") (pinfunction "S_26") (pintype "passive"))
      (node (ref "Q8") (pin "29") (pinfunction "S_29") (pintype "passive"))
      (node (ref "Q8") (pin "30") (pinfunction "S_30") (pintype "passive"))
      (node (ref "Q8") (pin "5") (pinfunction "S_5") (pintype "passive"))
      (node (ref "Q8") (pin "6") (pinfunction "S_6") (pintype "passive"))
      (node (ref "Q8") (pin "9") (pinfunction "S_9") (pintype "passive"))
      (node (ref "Q9") (pin "11") (pinfunction "D_11") (pintype "passive"))
      (node (ref "Q9") (pin "12") (pinfunction "D_12") (pintype "passive"))
      (node (ref "Q9") (pin "15") (pinfunction "D_15") (pintype "passive"))
      (node (ref "Q9") (pin "16") (pinfunction "D_16") (pintype "passive"))
      (node (ref "Q9") (pin "19") (pinfunction "D_19") (pintype "passive"))
      (node (ref "Q9") (pin "20") (pinfunction "D_20") (pintype "passive"))
      (node (ref "Q9") (pin "23") (pinfunction "D_23") (pintype "passive"))
      (node (ref "Q9") (pin "24") (pinfunction "D_24") (pintype "passive"))
      (node (ref "Q9") (pin "27") (pinfunction "D_27") (pintype "passive"))
      (node (ref "Q9") (pin "28") (pinfunction "D_28") (pintype "passive"))
      (node (ref "Q9") (pin "3") (pinfunction "D_3") (pintype "passive"))
      (node (ref "Q9") (pin "4") (pinfunction "D_4") (pintype "passive"))
      (node (ref "Q9") (pin "7") (pinfunction "D_7") (pintype "passive"))
      (node (ref "Q9") (pin "8") (pinfunction "D_8") (pintype "passive"))
      (node (ref "R31") (pin "1") (pinfunction "1_1") (pintype "passive"))
      (node (ref "R31") (pin "3") (pinfunction "1_3") (pintype "passive"))
      (node (ref "TP26") (pin "P$1") (pinfunction "P$1_P$1") (pintype "bidirectional"))
      (node (ref "U5") (pin "1C") (pinfunction "HS_1C") (pintype "bidirectional"))
      (node (ref "U5") (pin "4D") (pinfunction "HS_4D") (pintype "bidirectional"))
    )
    (net (code "41") (name "Net-(D7-PadA)") (class "Default")
      (node (ref "D7") (pin "A") (pinfunction "A_A") (pintype "passive"))
      (node (ref "R22") (pin "2") (pinfunction "2_2") (pintype "bidirectional"))
    )
    (net (code "42") (name "Net-(D11-PadA)") (class "Default")
      (node (ref "D11") (pin "A") (pinfunction "A_A") (pintype "passive"))
      (node (ref "R28") (pin "2") (pinfunction "2_2") (pintype "bidirectional"))
    )
    (net (code "43") (name "Net-(D15-PadA)") (class "Default")
      (node (ref "D15") (pin "A") (pinfunction "A_A") (pintype "passive"))
      (node (ref "R34") (pin "2") (pinfunction "2_2") (pintype "bidirectional"))
    )
    (net (code "44") (name "Net-(LED1-PadA)") (class "Default")
      (node (ref "LED1") (pin "A") (pinfunction "A_A") (pintype "passive"))
      (node (ref "R8") (pin "1") (pinfunction "1_1") (pintype "bidirectional"))
    )
    (net (code "45") (name "Net-(LED2-PadA)") (class "Default")
      (node (ref "LED2") (pin "A") (pinfunction "A_A") (pintype "passive"))
      (node (ref "R9") (pin "1") (pinfunction "1_1") (pintype "bidirectional"))
    )
    (net (code "46") (name "Net-(LED3-PadA)") (class "Default")
      (node (ref "LED3") (pin "A") (pinfunction "A_A") (pintype "passive"))
      (node (ref "R40") (pin "1") (pinfunction "1_1") (pintype "bidirectional"))
    )
    (net (code "47") (name "Net-(LED4-PadA)") (class "Default")
      (node (ref "LED4") (pin "A") (pinfunction "A_A") (pintype "passive"))
      (node (ref "R55") (pin "1") (pinfunction "1_1") (pintype "bidirectional"))
    )
    (net (code "48") (name "Net-(LED5-PadA)") (class "Default")
      (node (ref "LED5") (pin "A") (pinfunction "A_A") (pintype "passive"))
      (node (ref "R56") (pin "1") (pinfunction "1_1") (pintype "bidirectional"))
    )
    (net (code "49") (name "Net-(LED6-PadA)") (class "Default")
      (node (ref "LED6") (pin "A") (pinfunction "A_A") (pintype "passive"))
      (node (ref "R57") (pin "1") (pinfunction "1_1") (pintype "bidirectional"))
    )
    (net (code "50") (name "Net-(LED7-PadA)") (class "Default")
      (node (ref "LED7") (pin "A") (pinfunction "A_A") (pintype "passive"))
      (node (ref "R58") (pin "1") (pinfunction "1_1") (pintype "bidirectional"))
    )
    (net (code "51") (name "Net-(Q1A-B)") (class "Default")
      (node (ref "Q1") (pin "1") (pinfunction "B_1") (pintype "passive"))
      (node (ref "Q1") (pin "2") (pinfunction "B_2") (pintype "passive"))
      (node (ref "Q1") (pin "3") (pinfunction "C_3") (pintype "passive"))
      (node (ref "R11") (pin "2") (pinfunction "2_2") (pintype "bidirectional"))
    )
    (net (code "52") (name "Net-(Q2-B)") (class "Default")
      (node (ref "Q2") (pin "1") (pinfunction "B_1") (pintype "passive"))
      (node (ref "R12") (pin "2") (pinfunction "2_2") (pintype "bidirectional"))
    )
    (net (code "53") (name "Net-(Q2-C)") (class "Default")
      (node (ref "D2") (pin "A") (pinfunction "A_A") (pintype "passive"))
      (node (ref "Q2") (pin "3") (pinfunction "C_3") (pintype "passive"))
      (node (ref "Q3") (pin "1") (pinfunction "G_1") (pintype "passive"))
      (node (ref "R13") (pin "1") (pinfunction "1_1") (pintype "bidirectional"))
    )
    (net (code "54") (name "Net-(Q2-E)") (class "Default")
      (node (ref "Q2") (pin "2") (pinfunction "E_2") (pintype "passive"))
      (node (ref "R14") (pin "2") (pinfunction "2_2") (pintype "bidirectional"))
    )
    (net (code "55") (name "Net-(Q3-D)") (class "Default")
      (node (ref "Q3") (pin "3") (pinfunction "D_3") (pintype "passive"))
      (node (ref "R15") (pin "2") (pinfunction "2_2") (pintype "bidirectional"))
    )
    (net (code "56") (name "Net-(Q4-G)") (class "Default")
      (node (ref "Q4") (pin "1") (pinfunction "G_1") (pintype "passive"))
      (node (ref "R17") (pin "2") (pinfunction "2_2") (pintype "bidirectional"))
      (node (ref "TP18") (pin "P$1") (pinfunction "P$1_P$1") (pintype "bidirectional"))
      (node (ref "U3") (pin "1D") (pinfunction "HOL_1D") (pintype "bidirectional"))
    )
    (net (code "57") (name "Net-(Q5-G)") (class "Default")
      (node (ref "Q5") (pin "1") (pinfunction "G_1") (pintype "passive"))
      (node (ref "R18") (pin "2") (pinfunction "2_2") (pintype "bidirectional"))
      (node (ref "TP19") (pin "P$1") (pinfunction "P$1_P$1") (pintype "bidirectional"))
      (node (ref "U3") (pin "1A") (pinfunction "LOL_1A") (pintype "bidirectional"))
    )
    (net (code "58") (name "Net-(Q6-G)") (class "Default")
      (node (ref "Q6") (pin "1") (pinfunction "G_1") (pintype "passive"))
      (node (ref "R23") (pin "2") (pinfunction "2_2") (pintype "bidirectional"))
      (node (ref "TP21") (pin "P$1") (pinfunction "P$1_P$1") (pintype "bidirectional"))
      (node (ref "U4") (pin "1D") (pinfunction "HOL_1D") (pintype "bidirectional"))
    )
    (net (code "59") (name "Net-(Q7-G)") (class "Default")
      (node (ref "Q7") (pin "1") (pinfunction "G_1") (pintype "passive"))
      (node (ref "R24") (pin "2") (pinfunction "2_2") (pintype "bidirectional"))
      (node (ref "TP22") (pin "P$1") (pinfunction "P$1_P$1") (pintype "bidirectional"))
      (node (ref "U4") (pin "1A") (pinfunction "LOL_1A") (pintype "bidirectional"))
    )
    (net (code "60") (name "Net-(Q8-G)") (class "Default")
      (node (ref "Q8") (pin "1") (pinfunction "G_1") (pintype "passive"))
      (node (ref "R29") (pin "2") (pinfunction "2_2") (pintype "bidirectional"))
      (node (ref "TP24") (pin "P$1") (pinfunction "P$1_P$1") (pintype "bidirectional"))
      (node (ref "U5") (pin "1D") (pinfunction "HOL_1D") (pintype "bidirectional"))
    )
    (net (code "61") (name "Net-(Q9-G)") (class "Default")
      (node (ref "Q9") (pin "1") (pinfunction "G_1") (pintype "passive"))
      (node (ref "R30") (pin "2") (pinfunction "2_2") (pintype "bidirectional"))
      (node (ref "TP25") (pin "P$1") (pinfunction "P$1_P$1") (pintype "bidirectional"))
      (node (ref "U5") (pin "1A") (pinfunction "LOL_1A") (pintype "bidirectional"))
    )
    (net (code "62") (name "Net-(Q10-B)") (class "Default")
      (node (ref "C54") (pin "1") (pinfunction "1_1") (pintype "passive"))
      (node (ref "Q10") (pin "1") (pinfunction "B_1") (pintype "passive"))
      (node (ref "R41") (pin "1") (pinfunction "1_1") (pintype "bidirectional"))
      (node (ref "U8") (pin "1") (pinfunction "C_1") (pintype "passive"))
    )
    (net (code "63") (name "Net-(Q10-C)") (class "Default")
      (node (ref "C52") (pin "1") (pinfunction "1_1") (pintype "passive"))
      (node (ref "C53") (pin "1") (pinfunction "1_1") (pintype "passive"))
      (node (ref "L4") (pin "1") (pinfunction "1_1") (pintype "passive"))
      (node (ref "Q10") (pin "3") (pinfunction "C_3") (pintype "passive"))
      (node (ref "R41") (pin "2") (pinfunction "2_2") (pintype "bidirectional"))
    )
    (net (code "64") (name "Net-(Q11-D)") (class "Default")
      (node (ref "Q11") (pin "3") (pinfunction "D_3") (pintype "passive"))
      (node (ref "R52") (pin "1") (pinfunction "1_1") (pintype "bidirectional"))
      (node (ref "TP59") (pin "P$1") (pinfunction "P$1_P$1") (pintype "bidirectional"))
    )
    (net (code "65") (name "Net-(Q11-G)") (class "Default")
      (node (ref "Q11") (pin "1") (pinfunction "G_1") (pintype "passive"))
      (node (ref "U13") (pin "17") (pinfunction "PB1_17") (pintype "bidirectional"))
    )
    (net (code "66") (name "Net-(Q11-S)") (class "Default")
      (node (ref "Q11") (pin "2") (pinfunction "S_2") (pintype "passive"))
      (node (ref "R51") (pin "1") (pinfunction "1_1") (pintype "bidirectional"))
      (node (ref "U13") (pin "18") (pinfunction "PB2_18") (pintype "bidirectional"))
    )
    (net (code "67") (name "Net-(R35-Pad2)") (class "Default")
      (node (ref "R35") (pin "2") (pinfunction "2_2") (pintype "bidirectional"))
      (node (ref "TP42") (pin "P$1") (pinfunction "P$1_P$1") (pintype "bidirectional"))
    )
    (net (code "68") (name "Net-(U1-CBOOT)") (class "Default")
      (node (ref "C26") (pin "2") (pinfunction "2_2") (pintype "passive"))
      (node (ref "U1") (pin "3") (pinfunction "CBOOT_3") (pintype "bidirectional"))
    )
    (net (code "69") (name "Net-(U1-ENABLE)") (class "Default")
      (node (ref "R3") (pin "1") (pinfunction "1_1") (pintype "bidirectional"))
      (node (ref "R4") (pin "2") (pinfunction "2_2") (pintype "bidirectional"))
      (node (ref "U1") (pin "12") (pinfunction "ENABLE_12") (pintype "bidirectional"))
    )
    (net (code "70") (name "Net-(U1-FB)") (class "Default")
      (node (ref "C29") (pin "2") (pinfunction "2_2") (pintype "passive"))
      (node (ref "R6") (pin "1") (pinfunction "1_1") (pintype "bidirectional"))
      (node (ref "R7") (pin "2") (pinfunction "2_2") (pintype "bidirectional"))
      (node (ref "U1") (pin "9") (pinfunction "FB_9") (pintype "bidirectional"))
    )
    (net (code "71") (name "Net-(U1-RT)") (class "Default")
      (node (ref "R5") (pin "2") (pinfunction "2_2") (pintype "bidirectional"))
      (node (ref "U1") (pin "7") (pinfunction "RT_7") (pintype "bidirectional"))
    )
    (net (code "72") (name "Net-(U1-SS{slash}TRK)") (class "Default")
      (node (ref "C25") (pin "1") (pinfunction "1_1") (pintype "passive"))
      (node (ref "U1") (pin "11") (pinfunction "SS/TRK_11") (pintype "bidirectional"))
    )
    (net (code "73") (name "Net-(U1-VCC)") (class "Default")
      (node (ref "C27") (pin "1") (pinfunction "1_1") (pintype "passive"))
      (node (ref "U1") (pin "4") (pinfunction "VCC_4") (pintype "bidirectional"))
    )
    (net (code "74") (name "Net-(U2-BYPASS)") (class "Default")
      (node (ref "C33") (pin "1") (pinfunction "1_1") (pintype "passive"))
      (node (ref "U2") (pin "4") (pinfunction "BYPASS_4") (pintype "bidirectional"))
    )
    (net (code "75") (name "Net-(U3-HB)") (class "Default")
      (node (ref "C37") (pin "1") (pinfunction "1_1") (pintype "passive"))
      (node (ref "U3") (pin "3D") (pinfunction "HB_3D") (pintype "bidirectional"))
    )
    (net (code "76") (name "Net-(U3-HOH)") (class "Default")
      (node (ref "R17") (pin "1") (pinfunction "1_1") (pintype "bidirectional"))
      (node (ref "U3") (pin "2D") (pinfunction "HOH_2D") (pintype "bidirectional"))
    )
    (net (code "77") (name "Net-(U3-LOH)") (class "Default")
      (node (ref "R18") (pin "1") (pinfunction "1_1") (pintype "bidirectional"))
      (node (ref "U3") (pin "1B") (pinfunction "LOH_1B") (pintype "bidirectional"))
    )
    (net (code "78") (name "Net-(U4-HB)") (class "Default")
      (node (ref "C39") (pin "1") (pinfunction "1_1") (pintype "passive"))
      (node (ref "U4") (pin "3D") (pinfunction "HB_3D") (pintype "bidirectional"))
    )
    (net (code "79") (name "Net-(U4-HOH)") (class "Default")
      (node (ref "R23") (pin "1") (pinfunction "1_1") (pintype "bidirectional"))
      (node (ref "U4") (pin "2D") (pinfunction "HOH_2D") (pintype "bidirectional"))
    )
    (net (code "80") (name "Net-(U4-LOH)") (class "Default")
      (node (ref "R24") (pin "1") (pinfunction "1_1") (pintype "bidirectional"))
      (node (ref "U4") (pin "1B") (pinfunction "LOH_1B") (pintype "bidirectional"))
    )
    (net (code "81") (name "Net-(U5-HB)") (class "Default")
      (node (ref "C41") (pin "1") (pinfunction "1_1") (pintype "passive"))
      (node (ref "U5") (pin "3D") (pinfunction "HB_3D") (pintype "bidirectional"))
    )
    (net (code "82") (name "Net-(U5-HOH)") (class "Default")
      (node (ref "R29") (pin "1") (pinfunction "1_1") (pintype "bidirectional"))
      (node (ref "U5") (pin "2D") (pinfunction "HOH_2D") (pintype "bidirectional"))
    )
    (net (code "83") (name "Net-(U5-LOH)") (class "Default")
      (node (ref "R30") (pin "1") (pinfunction "1_1") (pintype "bidirectional"))
      (node (ref "U5") (pin "1B") (pinfunction "LOH_1B") (pintype "bidirectional"))
    )
    (net (code "84") (name "Net-(U7-IN)") (class "Default")
      (node (ref "C47") (pin "1") (pinfunction "1_1") (pintype "passive"))
      (node (ref "C48") (pin "1") (pinfunction "1_1") (pintype "passive"))
      (node (ref "L3") (pin "1") (pinfunction "1_1") (pintype "passive"))
      (node (ref "U7") (pin "3") (pinfunction "IN_3") (pintype "power_in"))
    )
    (net (code "85") (name "Net-(U8-REF)") (class "Default")
      (node (ref "C54") (pin "2") (pinfunction "2_2") (pintype "passive"))
      (node (ref "R42") (pin "1") (pinfunction "1_1") (pintype "bidirectional"))
      (node (ref "R43") (pin "2") (pinfunction "2_2") (pintype "bidirectional"))
      (node (ref "U8") (pin "2") (pinfunction "REF_2") (pintype "passive"))
    )
    (net (code "86") (name "Net-(U9-OUT)") (class "Default")
      (node (ref "R44") (pin "1") (pinfunction "1_1") (pintype "bidirectional"))
      (node (ref "U9") (pin "5") (pinfunction "OUT_5") (pintype "bidirectional"))
    )
    (net (code "87") (name "Net-(U9-REF2)") (class "Default")
      (node (ref "C57") (pin "1") (pinfunction "1_1") (pintype "passive"))
      (node (ref "C58") (pin "1") (pinfunction "1_1") (pintype "passive"))
      (node (ref "L5") (pin "1") (pinfunction "1_1") (pintype "passive"))
      (node (ref "U9") (pin "3") (pinfunction "REF2_3") (pintype "bidirectional"))
    )
    (net (code "88") (name "Net-(U9-VS)") (class "Default")
      (node (ref "C59") (pin "1") (pinfunction "1_1") (pintype "passive"))
      (node (ref "C60") (pin "1") (pinfunction "1_1") (pintype "passive"))
      (node (ref "L6") (pin "2") (pinfunction "2_2") (pintype "passive"))
      (node (ref "U9") (pin "6") (pinfunction "VS_6") (pintype "bidirectional"))
    )
    (net (code "89") (name "Net-(U10-OUT)") (class "Default")
      (node (ref "R45") (pin "1") (pinfunction "1_1") (pintype "bidirectional"))
      (node (ref "U10") (pin "5") (pinfunction "OUT_5") (pintype "bidirectional"))
    )
    (net (code "90") (name "Net-(U10-REF2)") (class "Default")
      (node (ref "C62") (pin "1") (pinfunction "1_1") (pintype "passive"))
      (node (ref "C63") (pin "1") (pinfunction "1_1") (pintype "passive"))
      (node (ref "L7") (pin "1") (pinfunction "1_1") (pintype "passive"))
      (node (ref "U10") (pin "3") (pinfunction "REF2_3") (pintype "bidirectional"))
    )
    (net (code "91") (name "Net-(U10-VS)") (class "Default")
      (node (ref "C64") (pin "1") (pinfunction "1_1") (pintype "passive"))
      (node (ref "C65") (pin "1") (pinfunction "1_1") (pintype "passive"))
      (node (ref "L8") (pin "2") (pinfunction "2_2") (pintype "passive"))
      (node (ref "U10") (pin "6") (pinfunction "VS_6") (pintype "bidirectional"))
    )
    (net (code "92") (name "Net-(U11-OUT)") (class "Default")
      (node (ref "R46") (pin "2") (pinfunction "2_2") (pintype "bidirectional"))
      (node (ref "U11") (pin "5") (pinfunction "OUT_5") (pintype "bidirectional"))
    )
    (net (code "93") (name "Net-(U11-REF2)") (class "Default")
      (node (ref "C67") (pin "1") (pinfunction "1_1") (pintype "passive"))
      (node (ref "C68") (pin "1") (pinfunction "1_1") (pintype "passive"))
      (node (ref "L9") (pin "1") (pinfunction "1_1") (pintype "passive"))
      (node (ref "U11") (pin "3") (pinfunction "REF2_3") (pintype "bidirectional"))
    )
    (net (code "94") (name "Net-(U11-VS)") (class "Default")
      (node (ref "C69") (pin "1") (pinfunction "1_1") (pintype "passive"))
      (node (ref "C70") (pin "1") (pinfunction "1_1") (pintype "passive"))
      (node (ref "L10") (pin "2") (pinfunction "2_2") (pintype "passive"))
      (node (ref "U11") (pin "6") (pinfunction "VS_6") (pintype "bidirectional"))
    )
    (net (code "95") (name "Net-(U13-PA0)") (class "Default")
      (node (ref "C74") (pin "1") (pinfunction "1_1") (pintype "passive"))
      (node (ref "R48") (pin "2") (pinfunction "2_2") (pintype "bidirectional"))
      (node (ref "TP46") (pin "P$1") (pinfunction "P$1_P$1") (pintype "bidirectional"))
      (node (ref "U13") (pin "8") (pinfunction "PA0_8") (pintype "bidirectional"))
    )
    (net (code "96") (name "Net-(U13-PA1)") (class "Default")
      (node (ref "C75") (pin "1") (pinfunction "1_1") (pintype "passive"))
      (node (ref "R49") (pin "2") (pinfunction "2_2") (pintype "bidirectional"))
      (node (ref "TP45") (pin "P$1") (pinfunction "P$1_P$1") (pintype "bidirectional"))
      (node (ref "U13") (pin "9") (pinfunction "PA1_9") (pintype "bidirectional"))
    )
    (net (code "97") (name "Net-(U13-PA3)") (class "Default")
      (node (ref "C77") (pin "1") (pinfunction "1_1") (pintype "passive"))
      (node (ref "R50") (pin "2") (pinfunction "2_2") (pintype "bidirectional"))
      (node (ref "TP49") (pin "P$1") (pinfunction "P$1_P$1") (pintype "bidirectional"))
      (node (ref "U13") (pin "11") (pinfunction "PA3_11") (pintype "bidirectional"))
    )
    (net (code "98") (name "Net-(U13-PB8-BOOT0)") (class "Default")
      (node (ref "R53") (pin "2") (pinfunction "2_2") (pintype "bidirectional"))
      (node (ref "U13") (pin "45") (pinfunction "PB8-BOOT0_45") (pintype "bidirectional"))
    )
    (net (code "99") (name "Net-(U13-PB11)") (class "Default")
      (node (ref "C85") (pin "1") (pinfunction "1_1") (pintype "passive"))
      (node (ref "R54") (pin "2") (pinfunction "2_2") (pintype "bidirectional"))
      (node (ref "TP51") (pin "P$1") (pinfunction "P$1_P$1") (pintype "bidirectional"))
      (node (ref "U13") (pin "25") (pinfunction "PB11_25") (pintype "bidirectional"))
    )
    (net (code "100") (name "Net-(U13-PF0-OSC_IN)") (class "Default")
      (node (ref "C78") (pin "2") (pinfunction "2_2") (pintype "passive"))
      (node (ref "U13") (pin "5") (pinfunction "PF0-OSC_IN_5") (pintype "bidirectional"))
      (node (ref "Y1") (pin "1") (pinfunction "1_1") (pintype "passive"))
    )
    (net (code "101") (name "Net-(U13-PF1-OSC_OUT)") (class "Default")
      (node (ref "C79") (pin "2") (pinfunction "2_2") (pintype "passive"))
      (node (ref "U13") (pin "6") (pinfunction "PF1-OSC_OUT_6") (pintype "bidirectional"))
      (node (ref "Y1") (pin "3") (pinfunction "2_3") (pintype "passive"))
    )
    (net (code "102") (name "Net-(U13-VDDA)") (class "Default")
      (node (ref "C80") (pin "1") (pinfunction "1_1") (pintype "passive"))
      (node (ref "C81") (pin "1") (pinfunction "1_1") (pintype "passive"))
      (node (ref "L11") (pin "2") (pinfunction "2_2") (pintype "passive"))
      (node (ref "U13") (pin "21") (pinfunction "VDDA_21") (pintype "bidirectional"))
    )
    (net (code "103") (name "Net-(U13-VREF)") (class "Default")
      (node (ref "C82") (pin "1") (pinfunction "1_1") (pintype "passive"))
      (node (ref "C83") (pin "1") (pinfunction "1_1") (pintype "passive"))
      (node (ref "L12") (pin "2") (pinfunction "2_2") (pintype "passive"))
      (node (ref "U13") (pin "20") (pinfunction "VREF_20") (pintype "bidirectional"))
    )
    (net (code "104") (name "PHASE_A") (class "Default")
      (node (ref "D5") (pin "C") (pinfunction "C_C") (pintype "passive"))
      (node (ref "J2") (pin "1") (pinfunction "1_1") (pintype "bidirectional"))
      (node (ref "R19") (pin "2") (pinfunction "2_2") (pintype "passive"))
      (node (ref "R19") (pin "4") (pinfunction "2_4") (pintype "passive"))
      (node (ref "R20") (pin "1") (pinfunction "1_1") (pintype "bidirectional"))
    )
    (net (code "105") (name "PHASE_A_CS_N") (class "Default")
      (node (ref "R19") (pin "2_SENSE") (pinfunction "2K_2_SENSE") (pintype "passive"))
      (node (ref "U9") (pin "1") (pinfunction "IN-_1") (pintype "bidirectional"))
    )
    (net (code "106") (name "PHASE_A_CS_P") (class "Default")
      (node (ref "R19") (pin "1_SENSE") (pinfunction "1K_1_SENSE") (pintype "passive"))
      (node (ref "U9") (pin "8") (pinfunction "IN+_8") (pintype "bidirectional"))
    )
    (net (code "107") (name "PHASE_B") (class "Default")
      (node (ref "D9") (pin "C") (pinfunction "C_C") (pintype "passive"))
      (node (ref "J3") (pin "1") (pinfunction "1_1") (pintype "bidirectional"))
      (node (ref "R25") (pin "2") (pinfunction "2_2") (pintype "passive"))
      (node (ref "R25") (pin "4") (pinfunction "2_4") (pintype "passive"))
      (node (ref "R26") (pin "1") (pinfunction "1_1") (pintype "bidirectional"))
    )
    (net (code "108") (name "PHASE_B_CS_N") (class "Default")
      (node (ref "R25") (pin "2_SENSE") (pinfunction "2K_2_SENSE") (pintype "passive"))
      (node (ref "U10") (pin "1") (pinfunction "IN-_1") (pintype "bidirectional"))
    )
    (net (code "109") (name "PHASE_B_CS_P") (class "Default")
      (node (ref "R25") (pin "1_SENSE") (pinfunction "1K_1_SENSE") (pintype "passive"))
      (node (ref "U10") (pin "8") (pinfunction "IN+_8") (pintype "bidirectional"))
    )
    (net (code "110") (name "PHASE_C") (class "Default")
      (node (ref "D13") (pin "C") (pinfunction "C_C") (pintype "passive"))
      (node (ref "J4") (pin "1") (pinfunction "1_1") (pintype "bidirectional"))
      (node (ref "R31") (pin "2") (pinfunction "2_2") (pintype "passive"))
      (node (ref "R31") (pin "4") (pinfunction "2_4") (pintype "passive"))
      (node (ref "R32") (pin "1") (pinfunction "1_1") (pintype "bidirectional"))
    )
    (net (code "111") (name "PHASE_C_CS_N") (class "Default")
      (node (ref "R31") (pin "2_SENSE") (pinfunction "2K_2_SENSE") (pintype "passive"))
      (node (ref "U11") (pin "1") (pinfunction "IN-_1") (pintype "bidirectional"))
    )
    (net (code "112") (name "PHASE_C_CS_P") (class "Default")
      (node (ref "R31") (pin "1_SENSE") (pinfunction "1K_1_SENSE") (pintype "passive"))
      (node (ref "U11") (pin "8") (pinfunction "IN+_8") (pintype "bidirectional"))
    )
    (net (code "113") (name "PWR_IN") (class "Default")
      (node (ref "D19") (pin "K") (pinfunction "C_K") (pintype "passive"))
      (node (ref "J5") (pin "1") (pinfunction "1_1") (pintype "bidirectional"))
      (node (ref "R2") (pin "1") (pinfunction "1_1") (pintype "bidirectional"))
    )
    (net (code "114") (name "RC_PWM_IN") (class "Default")
      (node (ref "D17") (pin "C") (pinfunction "C_C") (pintype "passive"))
      (node (ref "R35") (pin "1") (pinfunction "1_1") (pintype "bidirectional"))
      (node (ref "U13") (pin "41") (pinfunction "PB4_41") (pintype "bidirectional"))
    )
    (net (code "115") (name "SW1") (class "Default")
      (node (ref "C44") (pin "1") (pinfunction "1_1") (pintype "passive"))
      (node (ref "R37") (pin "1") (pinfunction "1_1") (pintype "bidirectional"))
      (node (ref "U13") (pin "3") (pinfunction "PC14-OSC32_IN_3") (pintype "bidirectional"))
    )
    (net (code "116") (name "SW1_ESD") (class "Default")
      (node (ref "D21") (pin "3") (pinfunction "3_3") (pintype "passive"))
      (node (ref "R36") (pin "2") (pinfunction "2_2") (pintype "bidirectional"))
      (node (ref "R37") (pin "2") (pinfunction "2_2") (pintype "bidirectional"))
      (node (ref "SB1") (pin "1") (pinfunction "A1_1") (pintype "bidirectional"))
      (node (ref "SB1") (pin "1'") (pinfunction "A2_1'") (pintype "bidirectional"))
    )
    (net (code "117") (name "SW2") (class "Default")
      (node (ref "C45") (pin "1") (pinfunction "1_1") (pintype "passive"))
      (node (ref "R39") (pin "1") (pinfunction "1_1") (pintype "bidirectional"))
      (node (ref "U13") (pin "4") (pinfunction "PC15-OSC32_OUT_4") (pintype "bidirectional"))
    )
    (net (code "118") (name "SW2_ESD") (class "Default")
      (node (ref "D21") (pin "4") (pinfunction "4_4") (pintype "passive"))
      (node (ref "R38") (pin "2") (pinfunction "2_2") (pintype "bidirectional"))
      (node (ref "R39") (pin "2") (pinfunction "2_2") (pintype "bidirectional"))
      (node (ref "SB2") (pin "1") (pinfunction "A1_1") (pintype "bidirectional"))
      (node (ref "SB2") (pin "1'") (pinfunction "A2_1'") (pintype "bidirectional"))
    )
    (net (code "119") (name "USART1_RX") (class "Default")
      (node (ref "D22") (pin "6") (pinfunction "6_6") (pintype "passive"))
      (node (ref "J6") (pin "13") (pinfunction "13_13") (pintype "bidirectional"))
      (node (ref "U13") (pin "44") (pinfunction "PB7_44") (pintype "bidirectional"))
    )
    (net (code "120") (name "USART1_TX") (class "Default")
      (node (ref "D22") (pin "4") (pinfunction "4_4") (pintype "passive"))
      (node (ref "J6") (pin "14") (pinfunction "14_14") (pintype "bidirectional"))
      (node (ref "U13") (pin "43") (pinfunction "PB6_43") (pintype "bidirectional"))
    )
    (net (code "121") (name "VIN") (class "Default")
      (node (ref "C1") (pin "+") (pinfunction "+_+") (pintype "passive"))
      (node (ref "C10") (pin "1") (pinfunction "1_1") (pintype "passive"))
      (node (ref "C11") (pin "1") (pinfunction "1_1") (pintype "passive"))
      (node (ref "C12") (pin "1") (pinfunction "1_1") (pintype "passive"))
      (node (ref "C13") (pin "1") (pinfunction "1_1") (pintype "passive"))
      (node (ref "C14") (pin "1") (pinfunction "1_1") (pintype "passive"))
      (node (ref "C15") (pin "1") (pinfunction "1_1") (pintype "passive"))
      (node (ref "C16") (pin "1") (pinfunction "1_1") (pintype "passive"))
      (node (ref "C17") (pin "1") (pinfunction "1_1") (pintype "passive"))
      (node (ref "C18") (pin "1") (pinfunction "1_1") (pintype "passive"))
      (node (ref "C19") (pin "1") (pinfunction "1_1") (pintype "passive"))
      (node (ref "C2") (pin "+") (pinfunction "+_+") (pintype "passive"))
      (node (ref "C20") (pin "1") (pinfunction "1_1") (pintype "passive"))
      (node (ref "C21") (pin "1") (pinfunction "1_1") (pintype "passive"))
      (node (ref "C22") (pin "1") (pinfunction "1_1") (pintype "passive"))
      (node (ref "C3") (pin "+") (pinfunction "+_+") (pintype "passive"))
      (node (ref "C4") (pin "1") (pinfunction "1_1") (pintype "passive"))
      (node (ref "C5") (pin "1") (pinfunction "1_1") (pintype "passive"))
      (node (ref "C6") (pin "1") (pinfunction "1_1") (pintype "passive"))
      (node (ref "C7") (pin "1") (pinfunction "1_1") (pintype "passive"))
      (node (ref "C8") (pin "1") (pinfunction "1_1") (pintype "passive"))
      (node (ref "C9") (pin "1") (pinfunction "1_1") (pintype "passive"))
      (node (ref "D1") (pin "K") (pinfunction "C_K") (pintype "passive"))
      (node (ref "D2") (pin "C") (pinfunction "C_C") (pintype "passive"))
      (node (ref "J1") (pin "2") (pinfunction "2_2") (pintype "bidirectional"))
      (node (ref "Q3") (pin "2") (pinfunction "S_2") (pintype "passive"))
      (node (ref "Q4") (pin "11") (pinfunction "D_11") (pintype "passive"))
      (node (ref "Q4") (pin "12") (pinfunction "D_12") (pintype "passive"))
      (node (ref "Q4") (pin "15") (pinfunction "D_15") (pintype "passive"))
      (node (ref "Q4") (pin "16") (pinfunction "D_16") (pintype "passive"))
      (node (ref "Q4") (pin "19") (pinfunction "D_19") (pintype "passive"))
      (node (ref "Q4") (pin "20") (pinfunction "D_20") (pintype "passive"))
      (node (ref "Q4") (pin "23") (pinfunction "D_23") (pintype "passive"))
      (node (ref "Q4") (pin "24") (pinfunction "D_24") (pintype "passive"))
      (node (ref "Q4") (pin "27") (pinfunction "D_27") (pintype "passive"))
      (node (ref "Q4") (pin "28") (pinfunction "D_28") (pintype "passive"))
      (node (ref "Q4") (pin "3") (pinfunction "D_3") (pintype "passive"))
      (node (ref "Q4") (pin "4") (pinfunction "D_4") (pintype "passive"))
      (node (ref "Q4") (pin "7") (pinfunction "D_7") (pintype "passive"))
      (node (ref "Q4") (pin "8") (pinfunction "D_8") (pintype "passive"))
      (node (ref "Q6") (pin "11") (pinfunction "D_11") (pintype "passive"))
      (node (ref "Q6") (pin "12") (pinfunction "D_12") (pintype "passive"))
      (node (ref "Q6") (pin "15") (pinfunction "D_15") (pintype "passive"))
      (node (ref "Q6") (pin "16") (pinfunction "D_16") (pintype "passive"))
      (node (ref "Q6") (pin "19") (pinfunction "D_19") (pintype "passive"))
      (node (ref "Q6") (pin "20") (pinfunction "D_20") (pintype "passive"))
      (node (ref "Q6") (pin "23") (pinfunction "D_23") (pintype "passive"))
      (node (ref "Q6") (pin "24") (pinfunction "D_24") (pintype "passive"))
      (node (ref "Q6") (pin "27") (pinfunction "D_27") (pintype "passive"))
      (node (ref "Q6") (pin "28") (pinfunction "D_28") (pintype "passive"))
      (node (ref "Q6") (pin "3") (pinfunction "D_3") (pintype "passive"))
      (node (ref "Q6") (pin "4") (pinfunction "D_4") (pintype "passive"))
      (node (ref "Q6") (pin "7") (pinfunction "D_7") (pintype "passive"))
      (node (ref "Q6") (pin "8") (pinfunction "D_8") (pintype "passive"))
      (node (ref "Q8") (pin "11") (pinfunction "D_11") (pintype "passive"))
      (node (ref "Q8") (pin "12") (pinfunction "D_12") (pintype "passive"))
      (node (ref "Q8") (pin "15") (pinfunction "D_15") (pintype "passive"))
      (node (ref "Q8") (pin "16") (pinfunction "D_16") (pintype "passive"))
      (node (ref "Q8") (pin "19") (pinfunction "D_19") (pintype "passive"))
      (node (ref "Q8") (pin "20") (pinfunction "D_20") (pintype "passive"))
      (node (ref "Q8") (pin "23") (pinfunction "D_23") (pintype "passive"))
      (node (ref "Q8") (pin "24") (pinfunction "D_24") (pintype "passive"))
      (node (ref "Q8") (pin "27") (pinfunction "D_27") (pintype "passive"))
      (node (ref "Q8") (pin "28") (pinfunction "D_28") (pintype "passive"))
      (node (ref "Q8") (pin "3") (pinfunction "D_3") (pintype "passive"))
      (node (ref "Q8") (pin "4") (pinfunction "D_4") (pintype "passive"))
      (node (ref "Q8") (pin "7") (pinfunction "D_7") (pintype "passive"))
      (node (ref "Q8") (pin "8") (pinfunction "D_8") (pintype "passive"))
      (node (ref "R1") (pin "1") (pinfunction "1_1") (pintype "bidirectional"))
      (node (ref "R13") (pin "2") (pinfunction "2_2") (pintype "bidirectional"))
      (node (ref "TP17") (pin "P$1") (pinfunction "P$1_P$1") (pintype "bidirectional"))
    )
    (net (code "122") (name "VIN_SENSE") (class "Default")
      (node (ref "C76") (pin "1") (pinfunction "1_1") (pintype "passive"))
      (node (ref "D3") (pin "A") (pinfunction "A_A") (pintype "passive"))
      (node (ref "D4") (pin "C") (pinfunction "C_C") (pintype "passive"))
      (node (ref "R15") (pin "1") (pinfunction "1_1") (pintype "bidirectional"))
      (node (ref "R16") (pin "2") (pinfunction "2_2") (pintype "bidirectional"))
      (node (ref "U13") (pin "10") (pinfunction "PA2_10") (pintype "bidirectional"))
    )
    (net (code "123") (name "VREF") (class "Default")
      (node (ref "C55") (pin "1") (pinfunction "1_1") (pintype "passive"))
      (node (ref "C56") (pin "1") (pinfunction "1_1") (pintype "passive"))
      (node (ref "L12") (pin "1") (pinfunction "1_1") (pintype "passive"))
      (node (ref "L5") (pin "2") (pinfunction "2_2") (pintype "passive"))
      (node (ref "L7") (pin "2") (pinfunction "2_2") (pintype "passive"))
      (node (ref "L9") (pin "2") (pinfunction "2_2") (pintype "passive"))
      (node (ref "Q10") (pin "2") (pinfunction "E_2") (pintype "passive"))
      (node (ref "R42") (pin "2") (pinfunction "2_2") (pintype "bidirectional"))
      (node (ref "TP43") (pin "P$1") (pinfunction "P$1_P$1") (pintype "bidirectional"))
    )
    (net (code "124") (name "unconnected-(AIM1-PadAIM)") (class "Default")
      (node (ref "AIM1") (pin "AIM") (pinfunction "AIM_AIM") (pintype "passive"))
    )
    (net (code "125") (name "unconnected-(AIM2-PadAIM)") (class "Default")
      (node (ref "AIM2") (pin "AIM") (pinfunction "AIM_AIM") (pintype "passive"))
    )
    (net (code "126") (name "unconnected-(AIM3-PadAIM)") (class "Default")
      (node (ref "AIM3") (pin "AIM") (pinfunction "AIM_AIM") (pintype "passive"))
    )
    (net (code "127") (name "unconnected-(AIM4-PadAIM)") (class "Default")
      (node (ref "AIM4") (pin "AIM") (pinfunction "AIM_AIM") (pintype "passive"))
    )
    (net (code "128") (name "unconnected-(AIM5-PadAIM)") (class "Default")
      (node (ref "AIM5") (pin "AIM") (pinfunction "AIM_AIM") (pintype "passive"))
    )
    (net (code "129") (name "unconnected-(AIM6-PadAIM)") (class "Default")
      (node (ref "AIM6") (pin "AIM") (pinfunction "AIM_AIM") (pintype "passive"))
    )
    (net (code "130") (name "unconnected-(D21-Pad1)") (class "Default")
      (node (ref "D21") (pin "1") (pinfunction "1_1") (pintype "passive"))
    )
    (net (code "131") (name "unconnected-(J6-Pad1)") (class "Default")
      (node (ref "J6") (pin "1") (pinfunction "1_1") (pintype "bidirectional"))
    )
    (net (code "132") (name "unconnected-(J6-Pad2)") (class "Default")
      (node (ref "J6") (pin "2") (pinfunction "2_2") (pintype "bidirectional"))
    )
    (net (code "133") (name "unconnected-(U1-PGOOD-Pad8)") (class "Default")
      (node (ref "U1") (pin "8") (pinfunction "PGOOD_8") (pintype "bidirectional"))
    )
    (net (code "134") (name "unconnected-(U12-VREF{slash}NC-Pad5)") (class "Default")
      (node (ref "U12") (pin "5") (pinfunction "VREF/NC_5") (pintype "bidirectional"))
    )
    (net (code "135") (name "~{NRST}") (class "Default")
      (node (ref "D22") (pin "5") (pinfunction "5_5") (pintype "passive"))
      (node (ref "J6") (pin "12") (pinfunction "12_12") (pintype "bidirectional"))
      (node (ref "U13") (pin "7") (pinfunction "PG10-NRST_7") (pintype "bidirectional"))
    )
  )
)
